# board2-4layer.net
KiCad netlist of a schematic drawn in EAGLE
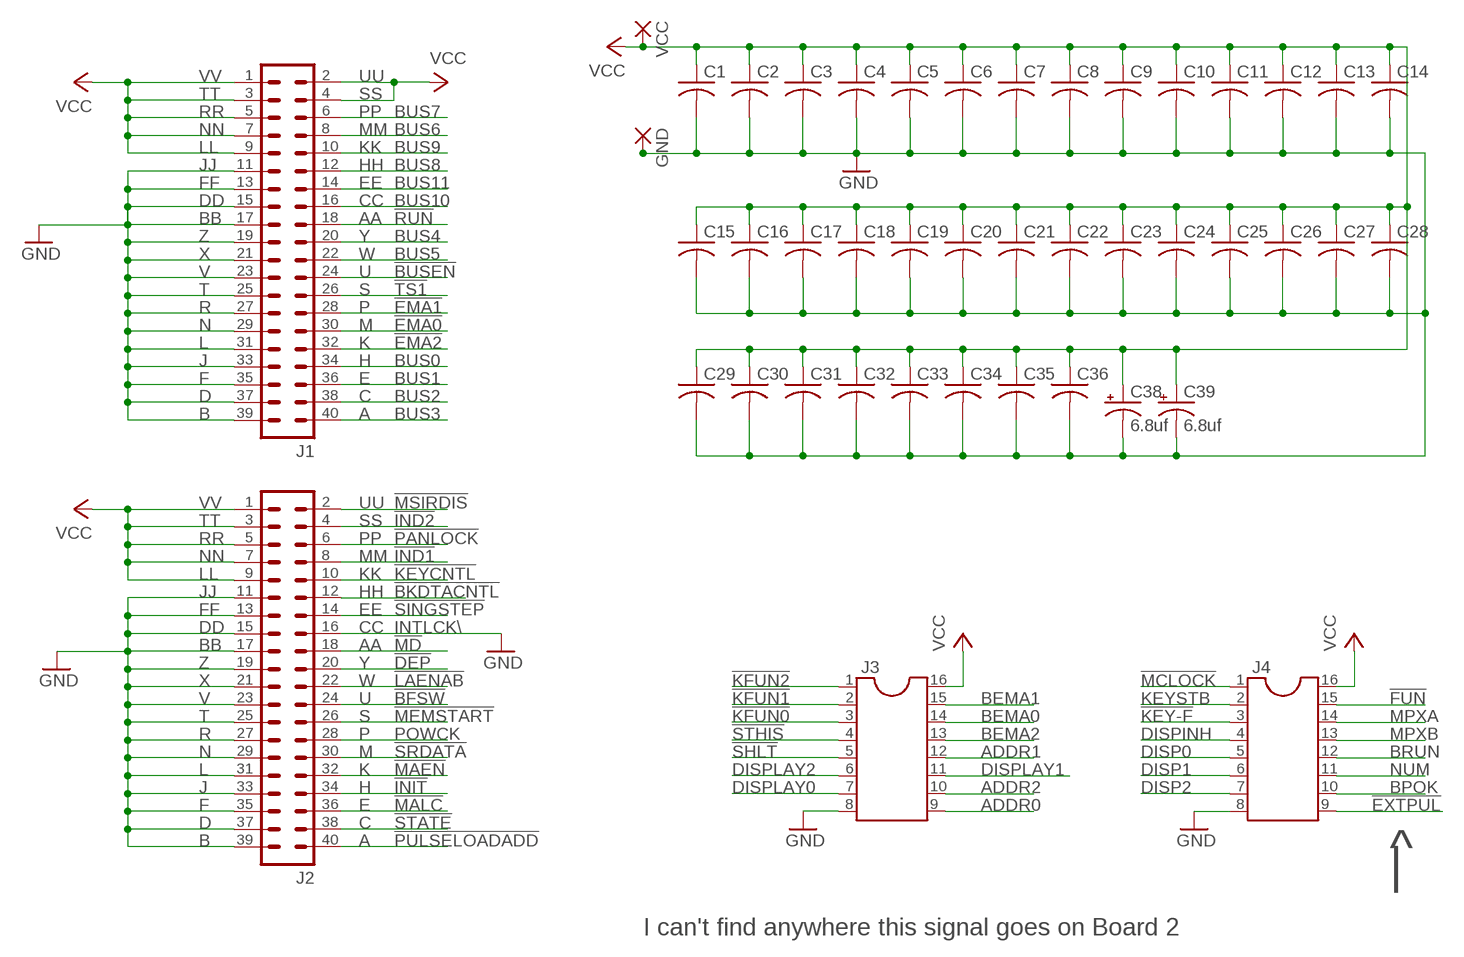
[diagram p0: schematic, sheet 1]
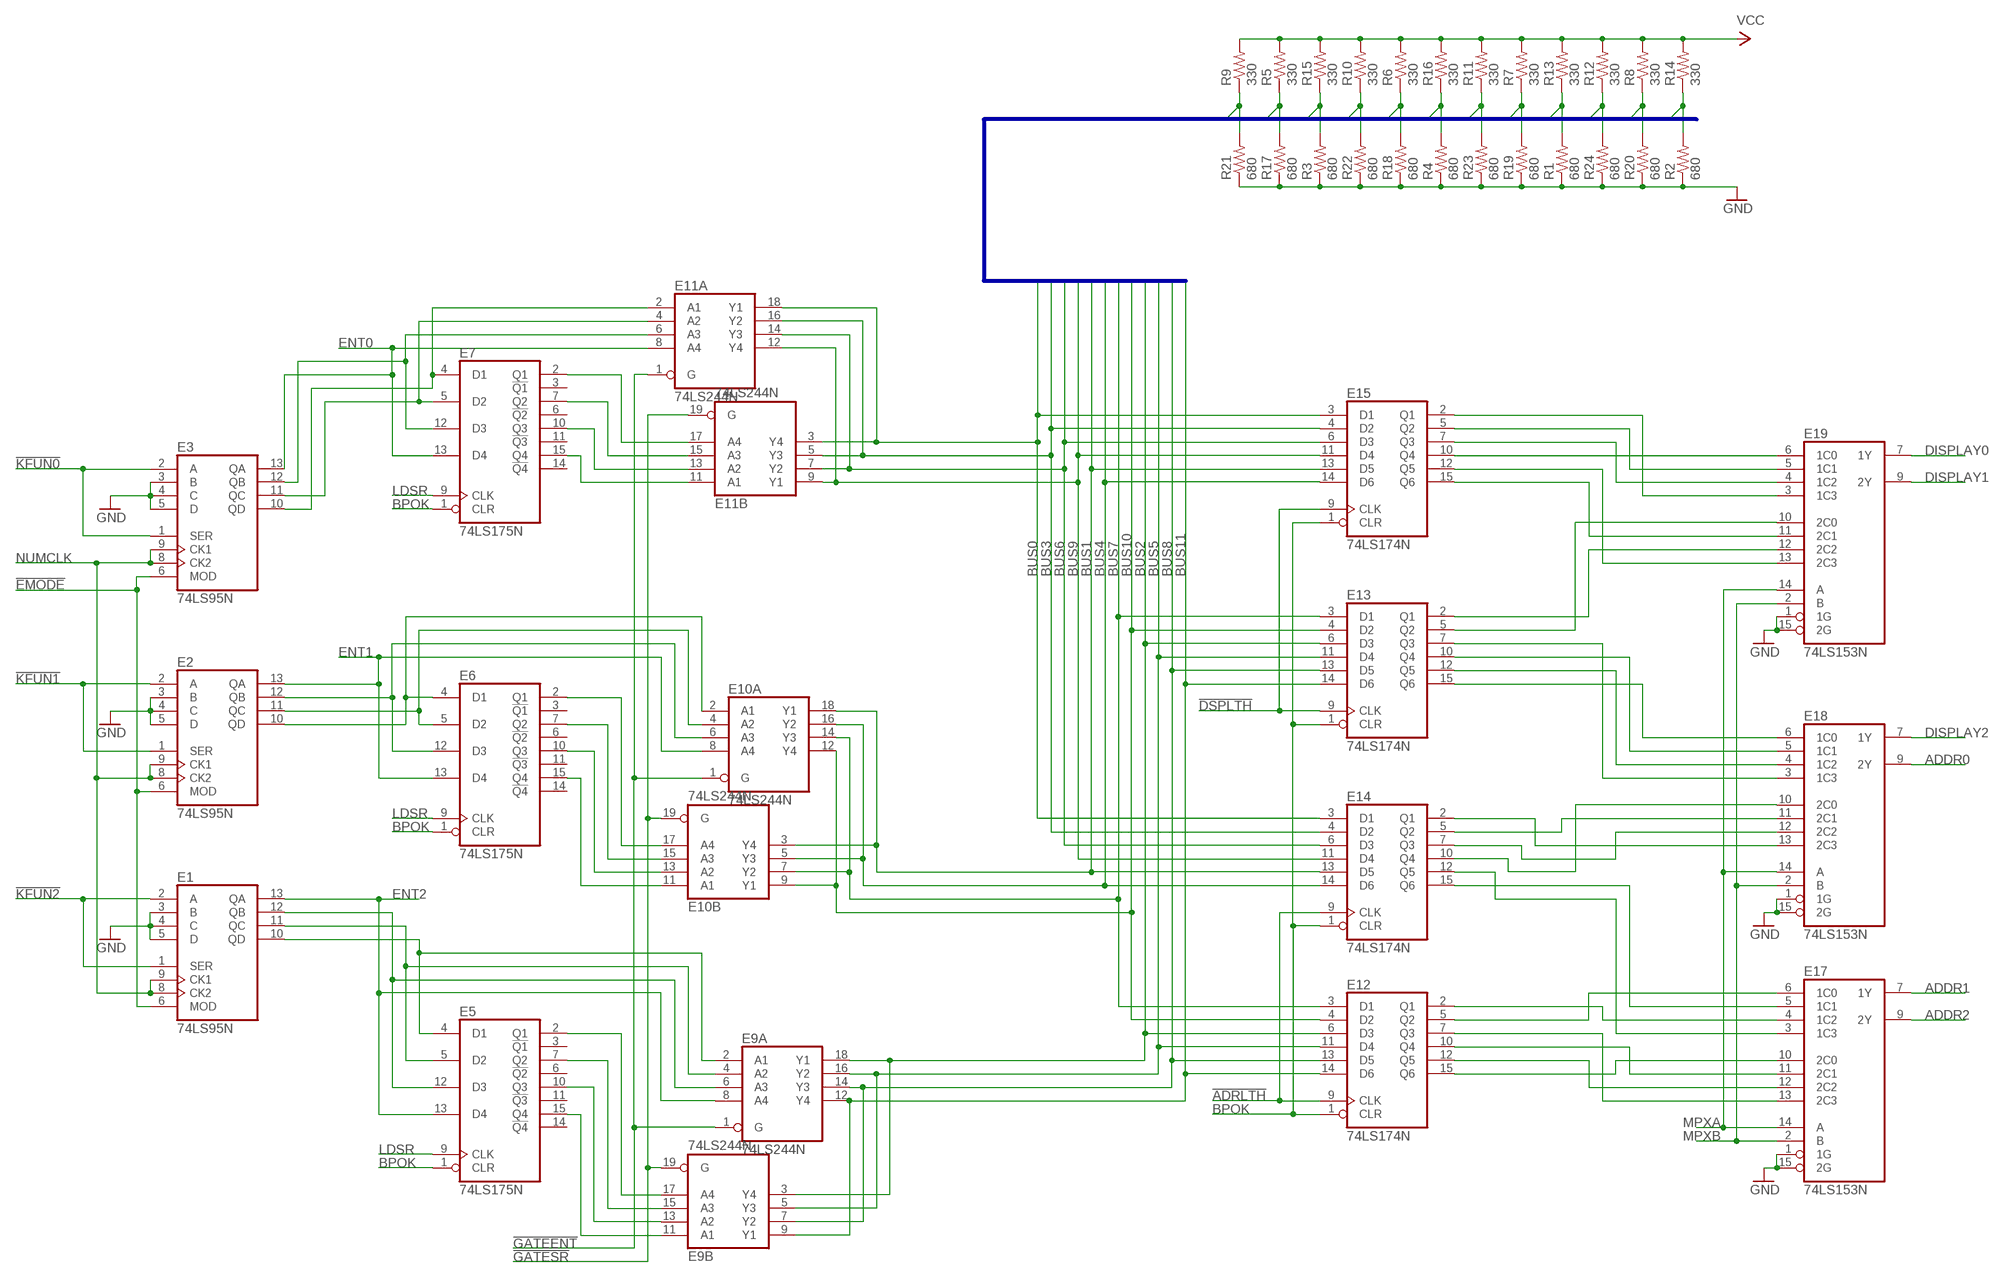
[diagram p1: schematic, sheet 2]
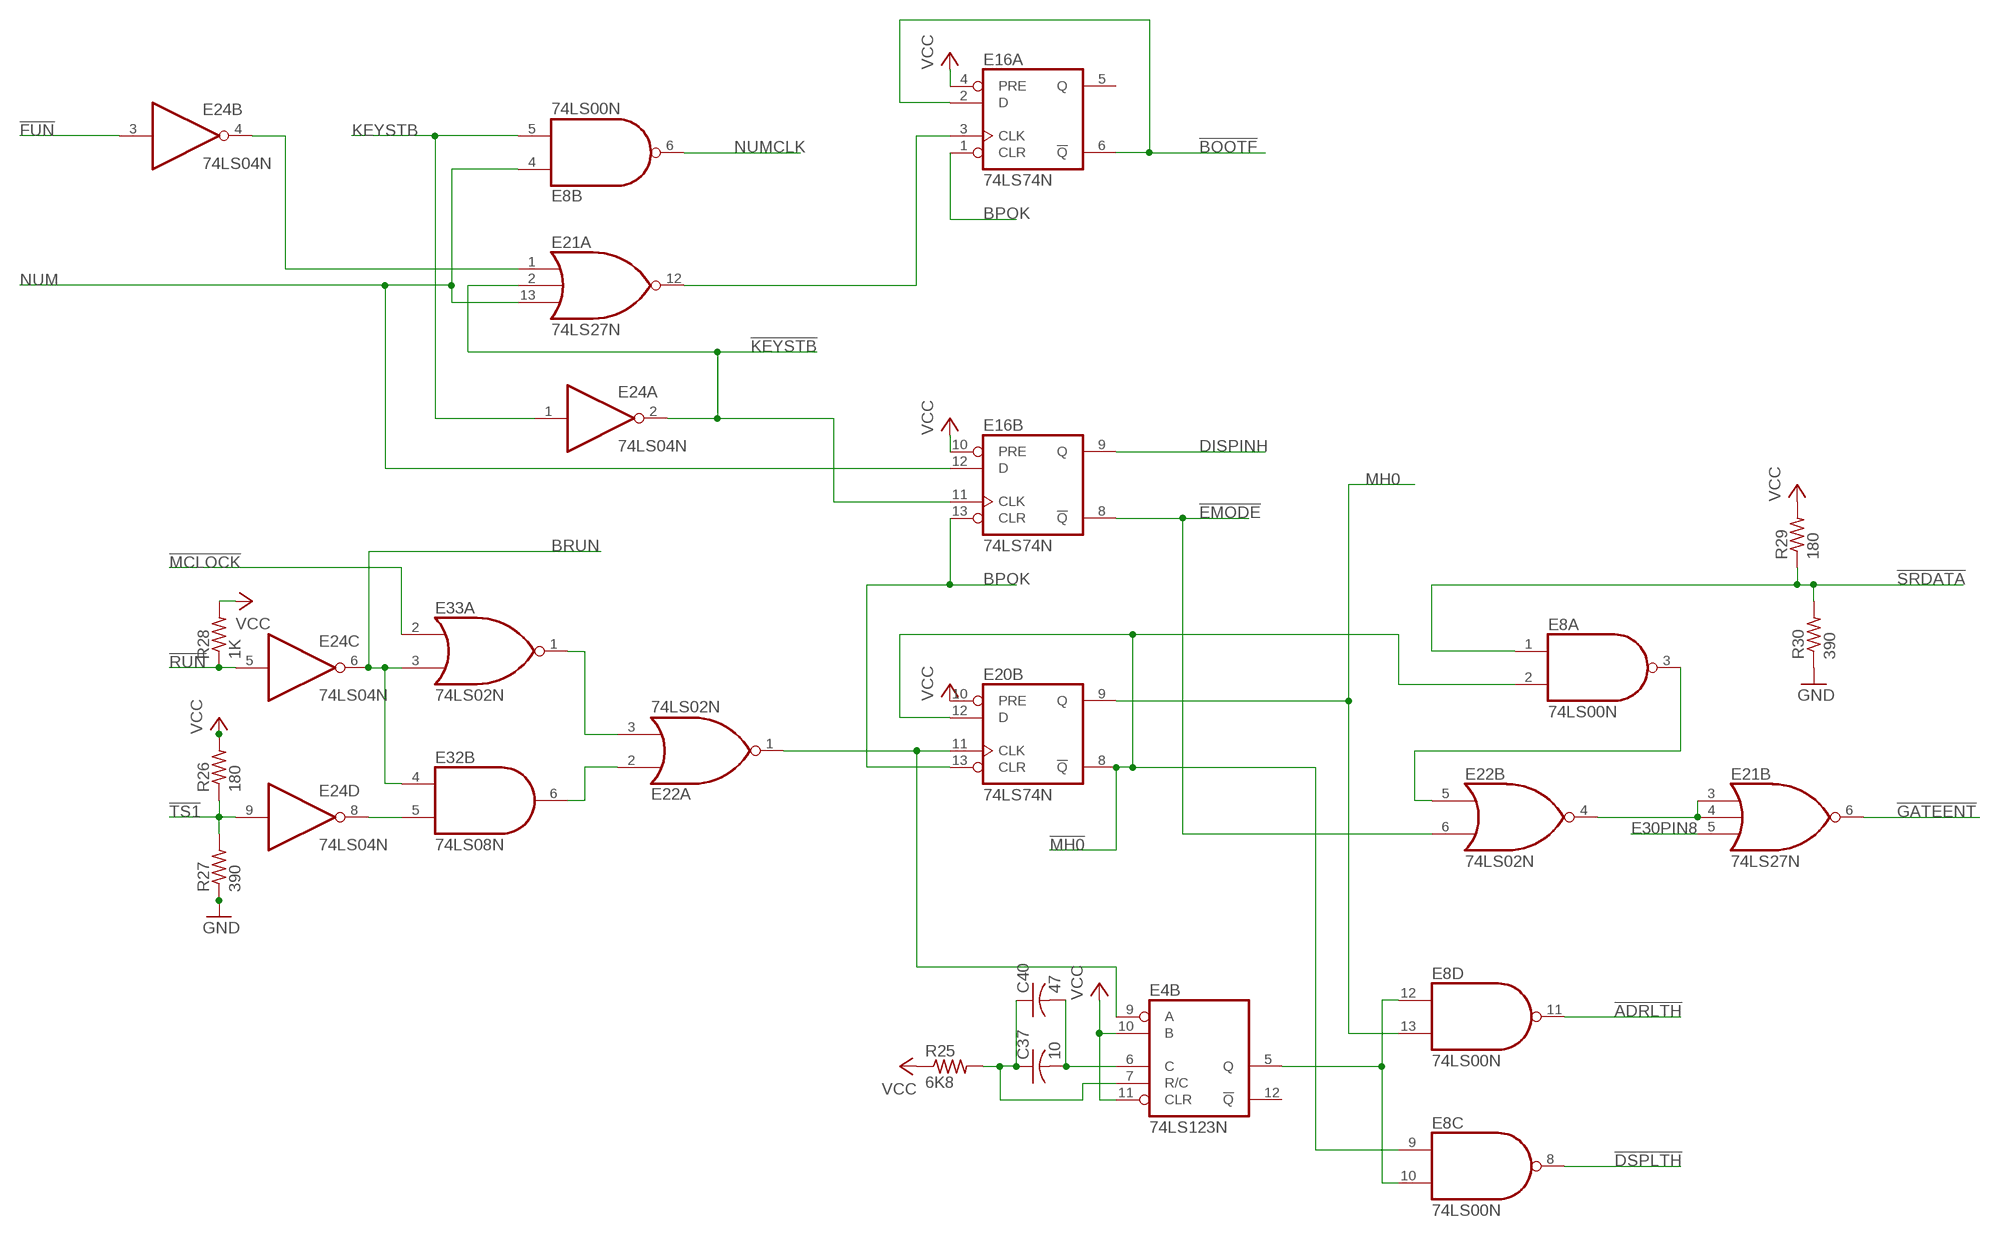
[diagram p2: schematic, sheet 3]
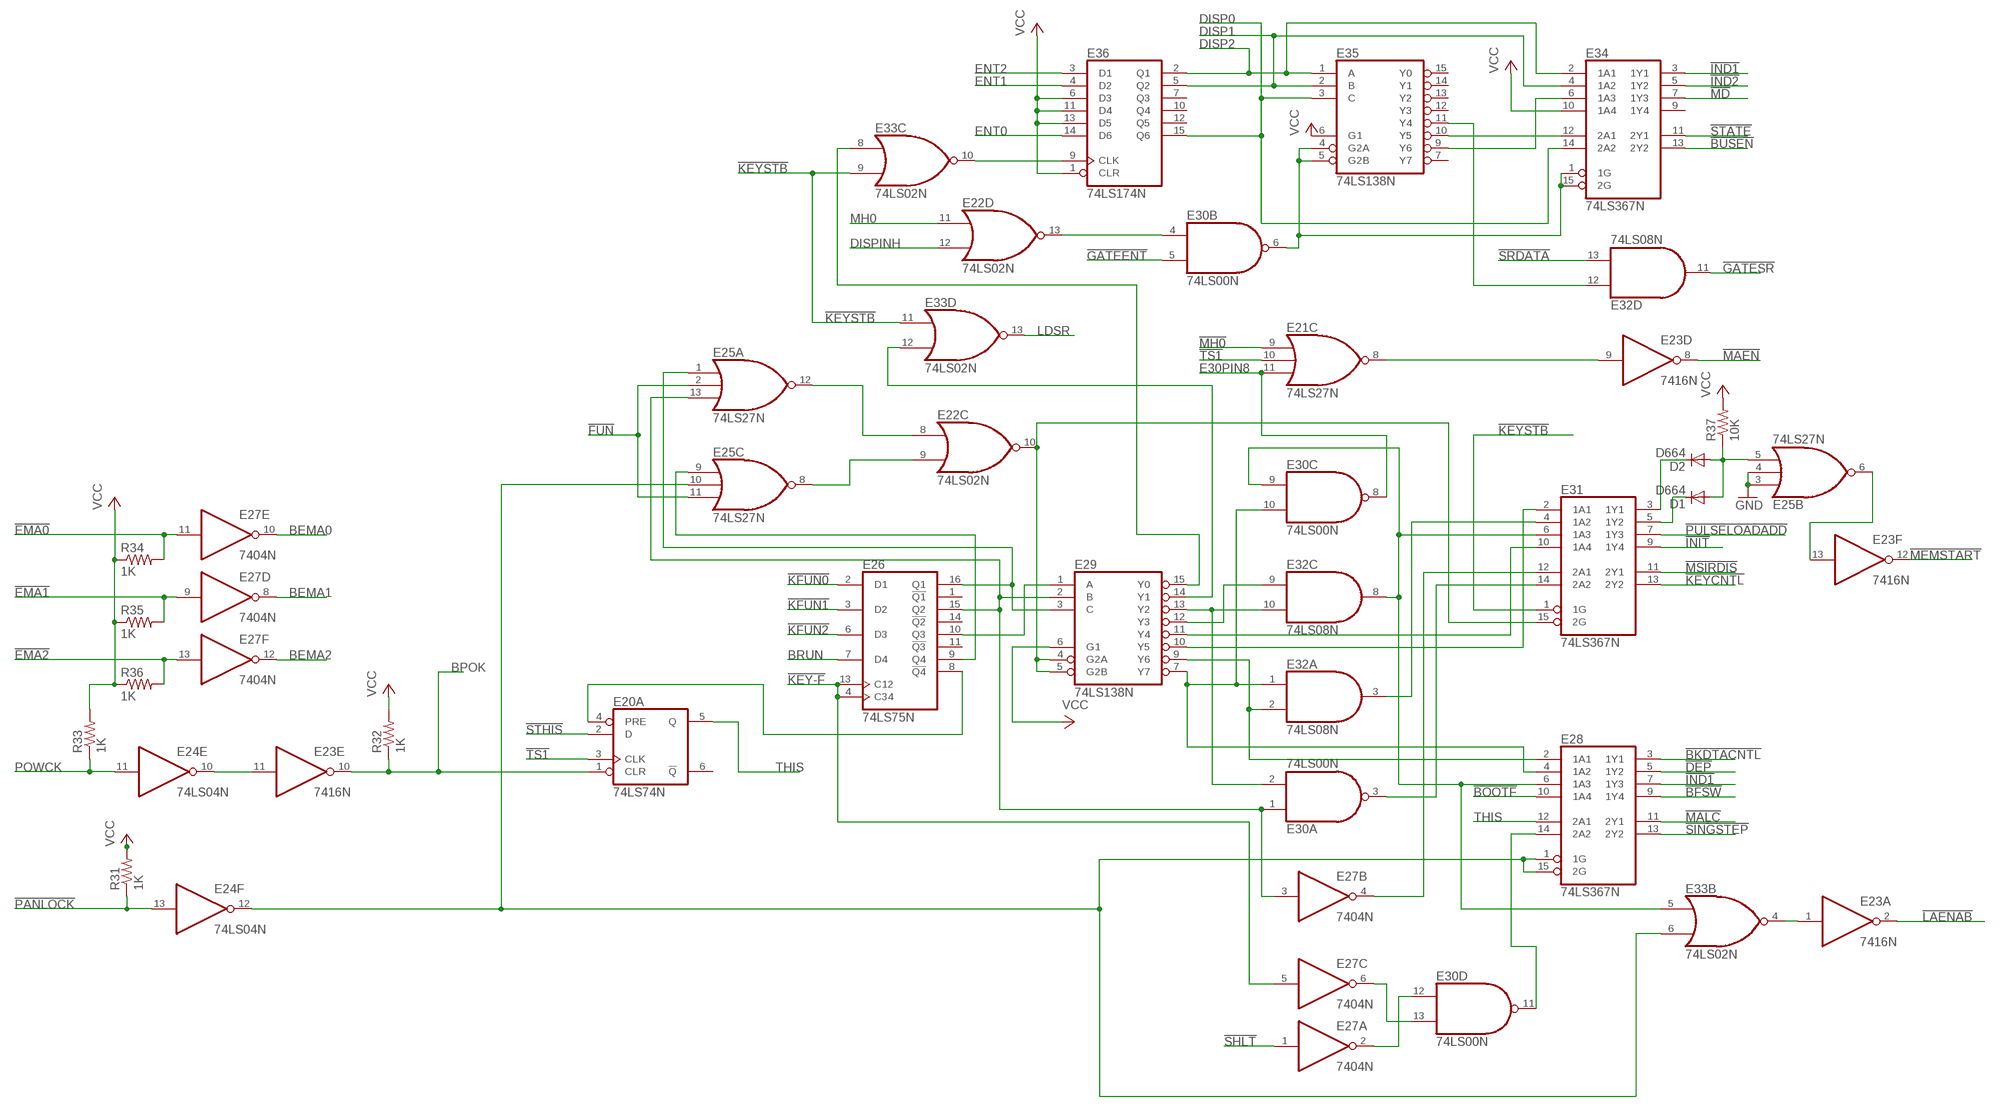
[diagram p3: schematic, sheet 4]

(export (version "E")
  (design (tool "Eeschema 10.0.6"))
  (components
    (comp (ref "C37")
      (value "10")
      (footprint "eagle-import:C050-025X075")
      (libsource (lib "eagle-import") (part "C-US050-025X075"))
    )
    (comp (ref "C40")
      (value "47")
      (footprint "eagle-import:C050-025X075")
      (libsource (lib "eagle-import") (part "C-US050-025X075"))
    )
    (comp (ref "E4")
      (value "74LS123N")
      (footprint "eagle-import:DIL16")
      (libsource (lib "eagle-import") (part "74123NLS"))
    )
    (comp (ref "E8")
      (value "74LS00N")
      (footprint "eagle-import:DIL14")
      (libsource (lib "eagle-import") (part "7400NLS"))
    )
    (comp (ref "E16")
      (value "74LS74N")
      (footprint "eagle-import:DIL14")
      (libsource (lib "eagle-import") (part "7474NLS"))
    )
    (comp (ref "E20")
      (value "74LS74N")
      (footprint "eagle-import:DIL14")
      (libsource (lib "eagle-import") (part "7474NLS"))
    )
    (comp (ref "E21")
      (value "74LS27N")
      (footprint "eagle-import:DIL14")
      (libsource (lib "eagle-import") (part "7427NLS"))
    )
    (comp (ref "E22")
      (value "74LS02N")
      (footprint "eagle-import:DIL14")
      (libsource (lib "eagle-import") (part "7402NLS"))
    )
    (comp (ref "E24")
      (value "74LS04N")
      (footprint "eagle-import:DIL14")
      (libsource (lib "eagle-import") (part "7404NLS"))
    )
    (comp (ref "E32")
      (value "74LS08N")
      (footprint "eagle-import:DIL14")
      (libsource (lib "eagle-import") (part "7408NLS"))
    )
    (comp (ref "E33")
      (value "74LS02N")
      (footprint "eagle-import:DIL14")
      (libsource (lib "eagle-import") (part "7402NLS"))
    )
    (comp (ref "R25")
      (value "6K8")
      (footprint "eagle-import:0207_10")
      (libsource (lib "eagle-import") (part "R-US_0207/10"))
    )
    (comp (ref "R26")
      (value "180")
      (footprint "eagle-import:0207_10")
      (libsource (lib "eagle-import") (part "R-US_0207/10"))
    )
    (comp (ref "R27")
      (value "390")
      (footprint "eagle-import:0207_10")
      (libsource (lib "eagle-import") (part "R-US_0207/10"))
    )
    (comp (ref "R28")
      (value "1K")
      (footprint "eagle-import:0207_10")
      (libsource (lib "eagle-import") (part "R-US_0207/10"))
    )
    (comp (ref "R29")
      (value "180")
      (footprint "eagle-import:0207_10")
      (libsource (lib "eagle-import") (part "R-US_0207/10"))
    )
    (comp (ref "R30")
      (value "390")
      (footprint "eagle-import:0207_10")
      (libsource (lib "eagle-import") (part "R-US_0207/10"))
    )
    (comp (ref "D1")
      (value "D664")
      (footprint "eagle-import:DO35-10")
      (libsource (lib "eagle-import") (part "1N4148DO35-10"))
    )
    (comp (ref "D2")
      (value "D664")
      (footprint "eagle-import:DO35-10")
      (libsource (lib "eagle-import") (part "1N4148DO35-10"))
    )
    (comp (ref "E23")
      (value "7416N")
      (footprint "eagle-import:DIL14")
      (libsource (lib "eagle-import") (part "7416N"))
    )
    (comp (ref "E25")
      (value "74LS27N")
      (footprint "eagle-import:DIL14")
      (libsource (lib "eagle-import") (part "7427NLS"))
    )
    (comp (ref "E26")
      (value "74LS75N")
      (footprint "eagle-import:DIL16")
      (libsource (lib "eagle-import") (part "7475NLS"))
    )
    (comp (ref "E27")
      (value "7404N")
      (footprint "eagle-import:DIL14")
      (libsource (lib "eagle-import") (part "7404N"))
    )
    (comp (ref "E28")
      (value "74LS367N")
      (footprint "eagle-import:DIL16")
      (libsource (lib "eagle-import") (part "74367N"))
    )
    (comp (ref "E29")
      (value "74LS138N")
      (footprint "eagle-import:DIL16")
      (libsource (lib "eagle-import") (part "74138NLS"))
    )
    (comp (ref "E30")
      (value "74LS00N")
      (footprint "eagle-import:DIL14")
      (libsource (lib "eagle-import") (part "7400NLS"))
    )
    (comp (ref "E31")
      (value "74LS367N")
      (footprint "eagle-import:DIL16")
      (libsource (lib "eagle-import") (part "74367N"))
    )
    (comp (ref "E34")
      (value "74LS367N")
      (footprint "eagle-import:DIL16")
      (libsource (lib "eagle-import") (part "74367N"))
    )
    (comp (ref "E35")
      (value "74LS138N")
      (footprint "eagle-import:DIL16")
      (libsource (lib "eagle-import") (part "74138NLS"))
    )
    (comp (ref "E36")
      (value "74LS174N")
      (footprint "eagle-import:DIL16")
      (libsource (lib "eagle-import") (part "74174NLS"))
    )
    (comp (ref "R31")
      (value "1K")
      (footprint "eagle-import:0207_10")
      (libsource (lib "eagle-import") (part "R-US_0207/10"))
    )
    (comp (ref "R32")
      (value "1K")
      (footprint "eagle-import:0207_10")
      (libsource (lib "eagle-import") (part "R-US_0207/10"))
    )
    (comp (ref "R33")
      (value "1K")
      (footprint "eagle-import:0207_10")
      (libsource (lib "eagle-import") (part "R-US_0207/10"))
    )
    (comp (ref "R34")
      (value "1K")
      (footprint "eagle-import:0207_10")
      (libsource (lib "eagle-import") (part "R-US_0207/10"))
    )
    (comp (ref "R35")
      (value "1K")
      (footprint "eagle-import:0207_10")
      (libsource (lib "eagle-import") (part "R-US_0207/10"))
    )
    (comp (ref "R36")
      (value "1K")
      (footprint "eagle-import:0207_10")
      (libsource (lib "eagle-import") (part "R-US_0207/10"))
    )
    (comp (ref "R37")
      (value "10K")
      (footprint "eagle-import:0207_10")
      (libsource (lib "eagle-import") (part "R-US_0207/10"))
    )
    (comp (ref "C1")
      (value "C-US050-025X075")
      (footprint "eagle-import:C050-025X075")
      (libsource (lib "eagle-import") (part "C-US050-025X075"))
    )
    (comp (ref "C2")
      (value "C-US050-025X075")
      (footprint "eagle-import:C050-025X075")
      (libsource (lib "eagle-import") (part "C-US050-025X075"))
    )
    (comp (ref "C3")
      (value "C-US050-025X075")
      (footprint "eagle-import:C050-025X075")
      (libsource (lib "eagle-import") (part "C-US050-025X075"))
    )
    (comp (ref "C4")
      (value "C-US050-025X075")
      (footprint "eagle-import:C050-025X075")
      (libsource (lib "eagle-import") (part "C-US050-025X075"))
    )
    (comp (ref "C5")
      (value "C-US050-025X075")
      (footprint "eagle-import:C050-025X075")
      (libsource (lib "eagle-import") (part "C-US050-025X075"))
    )
    (comp (ref "C6")
      (value "C-US050-025X075")
      (footprint "eagle-import:C050-025X075")
      (libsource (lib "eagle-import") (part "C-US050-025X075"))
    )
    (comp (ref "C7")
      (value "C-US050-025X075")
      (footprint "eagle-import:C050-025X075")
      (libsource (lib "eagle-import") (part "C-US050-025X075"))
    )
    (comp (ref "C8")
      (value "C-US050-025X075")
      (footprint "eagle-import:C050-025X075")
      (libsource (lib "eagle-import") (part "C-US050-025X075"))
    )
    (comp (ref "C9")
      (value "C-US050-025X075")
      (footprint "eagle-import:C050-025X075")
      (libsource (lib "eagle-import") (part "C-US050-025X075"))
    )
    (comp (ref "C10")
      (value "C-US050-025X075")
      (footprint "eagle-import:C050-025X075")
      (libsource (lib "eagle-import") (part "C-US050-025X075"))
    )
    (comp (ref "C11")
      (value "C-US050-025X075")
      (footprint "eagle-import:C050-025X075")
      (libsource (lib "eagle-import") (part "C-US050-025X075"))
    )
    (comp (ref "C12")
      (value "C-US050-025X075")
      (footprint "eagle-import:C050-025X075")
      (libsource (lib "eagle-import") (part "C-US050-025X075"))
    )
    (comp (ref "C13")
      (value "C-US050-025X075")
      (footprint "eagle-import:C050-025X075")
      (libsource (lib "eagle-import") (part "C-US050-025X075"))
    )
    (comp (ref "C14")
      (value "C-US050-025X075")
      (footprint "eagle-import:C050-025X075")
      (libsource (lib "eagle-import") (part "C-US050-025X075"))
    )
    (comp (ref "C15")
      (value "C-US050-025X075")
      (footprint "eagle-import:C050-025X075")
      (libsource (lib "eagle-import") (part "C-US050-025X075"))
    )
    (comp (ref "C16")
      (value "C-US050-025X075")
      (footprint "eagle-import:C050-025X075")
      (libsource (lib "eagle-import") (part "C-US050-025X075"))
    )
    (comp (ref "C17")
      (value "C-US050-025X075")
      (footprint "eagle-import:C050-025X075")
      (libsource (lib "eagle-import") (part "C-US050-025X075"))
    )
    (comp (ref "C18")
      (value "C-US050-025X075")
      (footprint "eagle-import:C050-025X075")
      (libsource (lib "eagle-import") (part "C-US050-025X075"))
    )
    (comp (ref "C19")
      (value "C-US050-025X075")
      (footprint "eagle-import:C050-025X075")
      (libsource (lib "eagle-import") (part "C-US050-025X075"))
    )
    (comp (ref "C20")
      (value "C-US050-025X075")
      (footprint "eagle-import:C050-025X075")
      (libsource (lib "eagle-import") (part "C-US050-025X075"))
    )
    (comp (ref "C21")
      (value "C-US050-025X075")
      (footprint "eagle-import:C050-025X075")
      (libsource (lib "eagle-import") (part "C-US050-025X075"))
    )
    (comp (ref "C22")
      (value "C-US050-025X075")
      (footprint "eagle-import:C050-025X075")
      (libsource (lib "eagle-import") (part "C-US050-025X075"))
    )
    (comp (ref "C23")
      (value "C-US050-025X075")
      (footprint "eagle-import:C050-025X075")
      (libsource (lib "eagle-import") (part "C-US050-025X075"))
    )
    (comp (ref "C24")
      (value "C-US050-025X075")
      (footprint "eagle-import:C050-025X075")
      (libsource (lib "eagle-import") (part "C-US050-025X075"))
    )
    (comp (ref "C25")
      (value "C-US050-025X075")
      (footprint "eagle-import:C050-025X075")
      (libsource (lib "eagle-import") (part "C-US050-025X075"))
    )
    (comp (ref "C26")
      (value "C-US050-025X075")
      (footprint "eagle-import:C050-025X075")
      (libsource (lib "eagle-import") (part "C-US050-025X075"))
    )
    (comp (ref "C27")
      (value "C-US050-025X075")
      (footprint "eagle-import:C050-025X075")
      (libsource (lib "eagle-import") (part "C-US050-025X075"))
    )
    (comp (ref "C28")
      (value "C-US050-025X075")
      (footprint "eagle-import:C050-025X075")
      (libsource (lib "eagle-import") (part "C-US050-025X075"))
    )
    (comp (ref "C29")
      (value "C-US050-025X075")
      (footprint "eagle-import:C050-025X075")
      (libsource (lib "eagle-import") (part "C-US050-025X075"))
    )
    (comp (ref "C30")
      (value "C-US050-025X075")
      (footprint "eagle-import:C050-025X075")
      (libsource (lib "eagle-import") (part "C-US050-025X075"))
    )
    (comp (ref "C31")
      (value "C-US050-025X075")
      (footprint "eagle-import:C050-025X075")
      (libsource (lib "eagle-import") (part "C-US050-025X075"))
    )
    (comp (ref "C32")
      (value "C-US050-025X075")
      (footprint "eagle-import:C050-025X075")
      (libsource (lib "eagle-import") (part "C-US050-025X075"))
    )
    (comp (ref "C33")
      (value "C-US050-025X075")
      (footprint "eagle-import:C050-025X075")
      (libsource (lib "eagle-import") (part "C-US050-025X075"))
    )
    (comp (ref "C34")
      (value "C-US050-025X075")
      (footprint "eagle-import:C050-025X075")
      (libsource (lib "eagle-import") (part "C-US050-025X075"))
    )
    (comp (ref "C35")
      (value "C-US050-025X075")
      (footprint "eagle-import:C050-025X075")
      (libsource (lib "eagle-import") (part "C-US050-025X075"))
    )
    (comp (ref "C36")
      (value "C-US050-025X075")
      (footprint "eagle-import:C050-025X075")
      (libsource (lib "eagle-import") (part "C-US050-025X075"))
    )
    (comp (ref "C38")
      (value "6.8uf")
      (footprint "eagle-import:E15-5")
      (libsource (lib "eagle-import") (part "CPOL-USE15-5AXIAL"))
    )
    (comp (ref "C39")
      (value "6.8uf")
      (footprint "eagle-import:E15-5")
      (libsource (lib "eagle-import") (part "CPOL-USE15-5AXIAL"))
    )
    (comp (ref "GND")
      (value "3,81/1,4")
      (footprint "eagle-import:3,81_1,4")
      (libsource (lib "eagle-import") (part "3,81/1,4"))
    )
    (comp (ref "J1")
      (value "40H")
      (footprint "eagle-import:40H")
      (libsource (lib "eagle-import") (part "40H"))
    )
    (comp (ref "J2")
      (value "40H")
      (footprint "eagle-import:40H")
      (libsource (lib "eagle-import") (part "40H"))
    )
    (comp (ref "J3")
      (value "DIL16S")
      (footprint "eagle-import:SOCKET-16")
      (libsource (lib "eagle-import") (part "DIL16S"))
    )
    (comp (ref "J4")
      (value "DIL16S")
      (footprint "eagle-import:SOCKET-16")
      (libsource (lib "eagle-import") (part "DIL16S"))
    )
    (comp (ref "VCC")
      (value "3,81/1,4")
      (footprint "eagle-import:3,81_1,4")
      (libsource (lib "eagle-import") (part "3,81/1,4"))
    )
    (comp (ref "E1")
      (value "74LS95N")
      (footprint "eagle-import:DIL14")
      (libsource (lib "eagle-import") (part "7495NLS"))
    )
    (comp (ref "E2")
      (value "74LS95N")
      (footprint "eagle-import:DIL14")
      (libsource (lib "eagle-import") (part "7495NLS"))
    )
    (comp (ref "E3")
      (value "74LS95N")
      (footprint "eagle-import:DIL14")
      (libsource (lib "eagle-import") (part "7495NLS"))
    )
    (comp (ref "E5")
      (value "74LS175N")
      (footprint "eagle-import:DIL16")
      (libsource (lib "eagle-import") (part "74175NLS"))
    )
    (comp (ref "E6")
      (value "74LS175N")
      (footprint "eagle-import:DIL16")
      (libsource (lib "eagle-import") (part "74175NLS"))
    )
    (comp (ref "E7")
      (value "74LS175N")
      (footprint "eagle-import:DIL16")
      (libsource (lib "eagle-import") (part "74175NLS"))
    )
    (comp (ref "E9")
      (value "74LS244N")
      (footprint "eagle-import:DIL20")
      (libsource (lib "eagle-import") (part "74244NS"))
    )
    (comp (ref "E10")
      (value "74LS244N")
      (footprint "eagle-import:DIL20")
      (libsource (lib "eagle-import") (part "74244NS"))
    )
    (comp (ref "E11")
      (value "74LS244N")
      (footprint "eagle-import:DIL20")
      (libsource (lib "eagle-import") (part "74244NS"))
    )
    (comp (ref "E12")
      (value "74LS174N")
      (footprint "eagle-import:DIL16")
      (libsource (lib "eagle-import") (part "74174NLS"))
    )
    (comp (ref "E13")
      (value "74LS174N")
      (footprint "eagle-import:DIL16")
      (libsource (lib "eagle-import") (part "74174NLS"))
    )
    (comp (ref "E14")
      (value "74LS174N")
      (footprint "eagle-import:DIL16")
      (libsource (lib "eagle-import") (part "74174NLS"))
    )
    (comp (ref "E15")
      (value "74LS174N")
      (footprint "eagle-import:DIL16")
      (libsource (lib "eagle-import") (part "74174NLS"))
    )
    (comp (ref "E17")
      (value "74LS153N")
      (footprint "eagle-import:DIL16")
      (libsource (lib "eagle-import") (part "74153NLS"))
    )
    (comp (ref "E18")
      (value "74LS153N")
      (footprint "eagle-import:DIL16")
      (libsource (lib "eagle-import") (part "74153NLS"))
    )
    (comp (ref "E19")
      (value "74LS153N")
      (footprint "eagle-import:DIL16")
      (libsource (lib "eagle-import") (part "74153NLS"))
    )
    (comp (ref "R1")
      (value "680")
      (footprint "eagle-import:0207_10")
      (libsource (lib "eagle-import") (part "R-US_0207/10"))
    )
    (comp (ref "R2")
      (value "680")
      (footprint "eagle-import:0207_10")
      (libsource (lib "eagle-import") (part "R-US_0207/10"))
    )
    (comp (ref "R3")
      (value "680")
      (footprint "eagle-import:0207_10")
      (libsource (lib "eagle-import") (part "R-US_0207/10"))
    )
    (comp (ref "R4")
      (value "680")
      (footprint "eagle-import:0207_10")
      (libsource (lib "eagle-import") (part "R-US_0207/10"))
    )
    (comp (ref "R5")
      (value "330")
      (footprint "eagle-import:0207_10")
      (libsource (lib "eagle-import") (part "R-US_0207/10"))
    )
    (comp (ref "R6")
      (value "330")
      (footprint "eagle-import:0207_10")
      (libsource (lib "eagle-import") (part "R-US_0207/10"))
    )
    (comp (ref "R7")
      (value "330")
      (footprint "eagle-import:0207_10")
      (libsource (lib "eagle-import") (part "R-US_0207/10"))
    )
    (comp (ref "R8")
      (value "330")
      (footprint "eagle-import:0207_10")
      (libsource (lib "eagle-import") (part "R-US_0207/10"))
    )
    (comp (ref "R9")
      (value "330")
      (footprint "eagle-import:0207_10")
      (libsource (lib "eagle-import") (part "R-US_0207/10"))
    )
    (comp (ref "R10")
      (value "330")
      (footprint "eagle-import:0207_10")
      (libsource (lib "eagle-import") (part "R-US_0207/10"))
    )
    (comp (ref "R11")
      (value "330")
      (footprint "eagle-import:0207_10")
      (libsource (lib "eagle-import") (part "R-US_0207/10"))
    )
    (comp (ref "R12")
      (value "330")
      (footprint "eagle-import:0207_10")
      (libsource (lib "eagle-import") (part "R-US_0207/10"))
    )
    (comp (ref "R13")
      (value "330")
      (footprint "eagle-import:0207_10")
      (libsource (lib "eagle-import") (part "R-US_0207/10"))
    )
    (comp (ref "R14")
      (value "330")
      (footprint "eagle-import:0207_10")
      (libsource (lib "eagle-import") (part "R-US_0207/10"))
    )
    (comp (ref "R15")
      (value "330")
      (footprint "eagle-import:0207_10")
      (libsource (lib "eagle-import") (part "R-US_0207/10"))
    )
    (comp (ref "R16")
      (value "330")
      (footprint "eagle-import:0207_10")
      (libsource (lib "eagle-import") (part "R-US_0207/10"))
    )
    (comp (ref "R17")
      (value "680")
      (footprint "eagle-import:0207_10")
      (libsource (lib "eagle-import") (part "R-US_0207/10"))
    )
    (comp (ref "R18")
      (value "680")
      (footprint "eagle-import:0207_10")
      (libsource (lib "eagle-import") (part "R-US_0207/10"))
    )
    (comp (ref "R19")
      (value "680")
      (footprint "eagle-import:0207_10")
      (libsource (lib "eagle-import") (part "R-US_0207/10"))
    )
    (comp (ref "R20")
      (value "680")
      (footprint "eagle-import:0207_10")
      (libsource (lib "eagle-import") (part "R-US_0207/10"))
    )
    (comp (ref "R21")
      (value "680")
      (footprint "eagle-import:0207_10")
      (libsource (lib "eagle-import") (part "R-US_0207/10"))
    )
    (comp (ref "R22")
      (value "680")
      (footprint "eagle-import:0207_10")
      (libsource (lib "eagle-import") (part "R-US_0207/10"))
    )
    (comp (ref "R23")
      (value "680")
      (footprint "eagle-import:0207_10")
      (libsource (lib "eagle-import") (part "R-US_0207/10"))
    )
    (comp (ref "R24")
      (value "680")
      (footprint "eagle-import:0207_10")
      (libsource (lib "eagle-import") (part "R-US_0207/10"))
    )
  )
  (nets
    (net (code "1") (name "ADDR0") (class "Default")
      (node (ref "E18") (pin "9") (pinfunction "2Y_9") (pintype "output"))
      (node (ref "J3") (pin "9") (pinfunction "9_9") (pintype "passive"))
    )
    (net (code "2") (name "ADDR1") (class "Default")
      (node (ref "E17") (pin "7") (pinfunction "1Y_7") (pintype "output"))
      (node (ref "J3") (pin "12") (pinfunction "12_12") (pintype "passive"))
    )
    (net (code "3") (name "ADDR2") (class "Default")
      (node (ref "E17") (pin "9") (pinfunction "2Y_9") (pintype "output"))
      (node (ref "J3") (pin "10") (pinfunction "10_10") (pintype "passive"))
    )
    (net (code "4") (name "BEMA0") (class "Default")
      (node (ref "E27") (pin "10") (pinfunction "O_10") (pintype "output"))
      (node (ref "J3") (pin "14") (pinfunction "14_14") (pintype "passive"))
    )
    (net (code "5") (name "BEMA1") (class "Default")
      (node (ref "E27") (pin "8") (pinfunction "O_8") (pintype "output"))
      (node (ref "J3") (pin "15") (pinfunction "15_15") (pintype "passive"))
    )
    (net (code "6") (name "BEMA2") (class "Default")
      (node (ref "E27") (pin "12") (pinfunction "O_12") (pintype "output"))
      (node (ref "J3") (pin "13") (pinfunction "13_13") (pintype "passive"))
    )
    (net (code "7") (name "BPOK") (class "Default")
      (node (ref "E12") (pin "1") (pinfunction "CLR_1") (pintype "input"))
      (node (ref "E13") (pin "1") (pinfunction "CLR_1") (pintype "input"))
      (node (ref "E14") (pin "1") (pinfunction "CLR_1") (pintype "input"))
      (node (ref "E15") (pin "1") (pinfunction "CLR_1") (pintype "input"))
      (node (ref "E16") (pin "1") (pinfunction "CLR_1") (pintype "input"))
      (node (ref "E16") (pin "13") (pinfunction "CLR_13") (pintype "input"))
      (node (ref "E20") (pin "1") (pinfunction "CLR_1") (pintype "input"))
      (node (ref "E20") (pin "13") (pinfunction "CLR_13") (pintype "input"))
      (node (ref "E23") (pin "10") (pinfunction "O_10") (pintype "open_collector"))
      (node (ref "E5") (pin "1") (pinfunction "CLR_1") (pintype "input"))
      (node (ref "E6") (pin "1") (pinfunction "CLR_1") (pintype "input"))
      (node (ref "E7") (pin "1") (pinfunction "CLR_1") (pintype "input"))
      (node (ref "J4") (pin "10") (pinfunction "10_10") (pintype "passive"))
      (node (ref "R32") (pin "1") (pinfunction "1_1") (pintype "passive"))
    )
    (net (code "8") (name "BRUN") (class "Default")
      (node (ref "E24") (pin "6") (pinfunction "O_6") (pintype "output"))
      (node (ref "E26") (pin "7") (pinfunction "D4_7") (pintype "input"))
      (node (ref "E32") (pin "4") (pinfunction "I0_4") (pintype "input"))
      (node (ref "E33") (pin "3") (pinfunction "I1_3") (pintype "input"))
      (node (ref "J4") (pin "12") (pinfunction "12_12") (pintype "passive"))
    )
    (net (code "9") (name "BUS0") (class "Default")
      (node (ref "E11") (pin "18") (pinfunction "Y1_18") (pintype "tri_state"))
      (node (ref "E11") (pin "3") (pinfunction "Y4_3") (pintype "tri_state"))
      (node (ref "E14") (pin "3") (pinfunction "D1_3") (pintype "input"))
      (node (ref "E15") (pin "3") (pinfunction "D1_3") (pintype "input"))
      (node (ref "J1") (pin "34") (pinfunction "34_34") (pintype "passive"))
      (node (ref "R21") (pin "2") (pinfunction "2_2") (pintype "passive"))
      (node (ref "R9") (pin "1") (pinfunction "1_1") (pintype "passive"))
    )
    (net (code "10") (name "BUS1") (class "Default")
      (node (ref "E10") (pin "18") (pinfunction "Y1_18") (pintype "tri_state"))
      (node (ref "E10") (pin "3") (pinfunction "Y4_3") (pintype "tri_state"))
      (node (ref "E14") (pin "13") (pinfunction "D5_13") (pintype "input"))
      (node (ref "E15") (pin "13") (pinfunction "D5_13") (pintype "input"))
      (node (ref "J1") (pin "36") (pinfunction "36_36") (pintype "passive"))
      (node (ref "R17") (pin "2") (pinfunction "2_2") (pintype "passive"))
      (node (ref "R5") (pin "1") (pinfunction "1_1") (pintype "passive"))
    )
    (net (code "11") (name "BUS2") (class "Default")
      (node (ref "E12") (pin "6") (pinfunction "D3_6") (pintype "input"))
      (node (ref "E13") (pin "6") (pinfunction "D3_6") (pintype "input"))
      (node (ref "E9") (pin "18") (pinfunction "Y1_18") (pintype "tri_state"))
      (node (ref "E9") (pin "3") (pinfunction "Y4_3") (pintype "tri_state"))
      (node (ref "J1") (pin "38") (pinfunction "38_38") (pintype "passive"))
      (node (ref "R15") (pin "1") (pinfunction "1_1") (pintype "passive"))
      (node (ref "R3") (pin "2") (pinfunction "2_2") (pintype "passive"))
    )
    (net (code "12") (name "BUS3") (class "Default")
      (node (ref "E11") (pin "16") (pinfunction "Y2_16") (pintype "tri_state"))
      (node (ref "E11") (pin "5") (pinfunction "Y3_5") (pintype "tri_state"))
      (node (ref "E14") (pin "4") (pinfunction "D2_4") (pintype "input"))
      (node (ref "E15") (pin "4") (pinfunction "D2_4") (pintype "input"))
      (node (ref "J1") (pin "40") (pinfunction "40_40") (pintype "passive"))
      (node (ref "R10") (pin "1") (pinfunction "1_1") (pintype "passive"))
      (node (ref "R22") (pin "2") (pinfunction "2_2") (pintype "passive"))
    )
    (net (code "13") (name "BUS4") (class "Default")
      (node (ref "E10") (pin "16") (pinfunction "Y2_16") (pintype "tri_state"))
      (node (ref "E10") (pin "5") (pinfunction "Y3_5") (pintype "tri_state"))
      (node (ref "E14") (pin "14") (pinfunction "D6_14") (pintype "input"))
      (node (ref "E15") (pin "14") (pinfunction "D6_14") (pintype "input"))
      (node (ref "J1") (pin "20") (pinfunction "20_20") (pintype "passive"))
      (node (ref "R18") (pin "2") (pinfunction "2_2") (pintype "passive"))
      (node (ref "R6") (pin "1") (pinfunction "1_1") (pintype "passive"))
    )
    (net (code "14") (name "BUS5") (class "Default")
      (node (ref "E12") (pin "11") (pinfunction "D4_11") (pintype "input"))
      (node (ref "E13") (pin "11") (pinfunction "D4_11") (pintype "input"))
      (node (ref "E9") (pin "16") (pinfunction "Y2_16") (pintype "tri_state"))
      (node (ref "E9") (pin "5") (pinfunction "Y3_5") (pintype "tri_state"))
      (node (ref "J1") (pin "22") (pinfunction "22_22") (pintype "passive"))
      (node (ref "R16") (pin "1") (pinfunction "1_1") (pintype "passive"))
      (node (ref "R4") (pin "2") (pinfunction "2_2") (pintype "passive"))
    )
    (net (code "15") (name "BUS6") (class "Default")
      (node (ref "E11") (pin "14") (pinfunction "Y3_14") (pintype "tri_state"))
      (node (ref "E11") (pin "7") (pinfunction "Y2_7") (pintype "tri_state"))
      (node (ref "E14") (pin "6") (pinfunction "D3_6") (pintype "input"))
      (node (ref "E15") (pin "6") (pinfunction "D3_6") (pintype "input"))
      (node (ref "J1") (pin "8") (pinfunction "8_8") (pintype "passive"))
      (node (ref "R11") (pin "1") (pinfunction "1_1") (pintype "passive"))
      (node (ref "R23") (pin "2") (pinfunction "2_2") (pintype "passive"))
    )
    (net (code "16") (name "BUS7") (class "Default")
      (node (ref "E10") (pin "14") (pinfunction "Y3_14") (pintype "tri_state"))
      (node (ref "E10") (pin "7") (pinfunction "Y2_7") (pintype "tri_state"))
      (node (ref "E12") (pin "3") (pinfunction "D1_3") (pintype "input"))
      (node (ref "E13") (pin "3") (pinfunction "D1_3") (pintype "input"))
      (node (ref "J1") (pin "6") (pinfunction "6_6") (pintype "passive"))
      (node (ref "R19") (pin "2") (pinfunction "2_2") (pintype "passive"))
      (node (ref "R7") (pin "1") (pinfunction "1_1") (pintype "passive"))
    )
    (net (code "17") (name "BUS8") (class "Default")
      (node (ref "E12") (pin "13") (pinfunction "D5_13") (pintype "input"))
      (node (ref "E13") (pin "13") (pinfunction "D5_13") (pintype "input"))
      (node (ref "E9") (pin "14") (pinfunction "Y3_14") (pintype "tri_state"))
      (node (ref "E9") (pin "7") (pinfunction "Y2_7") (pintype "tri_state"))
      (node (ref "J1") (pin "12") (pinfunction "12_12") (pintype "passive"))
      (node (ref "R1") (pin "2") (pinfunction "2_2") (pintype "passive"))
      (node (ref "R13") (pin "1") (pinfunction "1_1") (pintype "passive"))
    )
    (net (code "18") (name "BUS9") (class "Default")
      (node (ref "E11") (pin "12") (pinfunction "Y4_12") (pintype "tri_state"))
      (node (ref "E11") (pin "9") (pinfunction "Y1_9") (pintype "tri_state"))
      (node (ref "E14") (pin "11") (pinfunction "D4_11") (pintype "input"))
      (node (ref "E15") (pin "11") (pinfunction "D4_11") (pintype "input"))
      (node (ref "J1") (pin "10") (pinfunction "10_10") (pintype "passive"))
      (node (ref "R12") (pin "1") (pinfunction "1_1") (pintype "passive"))
      (node (ref "R24") (pin "2") (pinfunction "2_2") (pintype "passive"))
    )
    (net (code "19") (name "BUS10") (class "Default")
      (node (ref "E10") (pin "12") (pinfunction "Y4_12") (pintype "tri_state"))
      (node (ref "E10") (pin "9") (pinfunction "Y1_9") (pintype "tri_state"))
      (node (ref "E12") (pin "4") (pinfunction "D2_4") (pintype "input"))
      (node (ref "E13") (pin "4") (pinfunction "D2_4") (pintype "input"))
      (node (ref "J1") (pin "16") (pinfunction "16_16") (pintype "passive"))
      (node (ref "R20") (pin "2") (pinfunction "2_2") (pintype "passive"))
      (node (ref "R8") (pin "1") (pinfunction "1_1") (pintype "passive"))
    )
    (net (code "20") (name "BUS11") (class "Default")
      (node (ref "E12") (pin "14") (pinfunction "D6_14") (pintype "input"))
      (node (ref "E13") (pin "14") (pinfunction "D6_14") (pintype "input"))
      (node (ref "E9") (pin "12") (pinfunction "Y4_12") (pintype "tri_state"))
      (node (ref "E9") (pin "9") (pinfunction "Y1_9") (pintype "tri_state"))
      (node (ref "J1") (pin "14") (pinfunction "14_14") (pintype "passive"))
      (node (ref "R14") (pin "1") (pinfunction "1_1") (pintype "passive"))
      (node (ref "R2") (pin "2") (pinfunction "2_2") (pintype "passive"))
    )
    (net (code "21") (name "DISP0") (class "Default")
      (node (ref "E34") (pin "14") (pinfunction "2A2_14") (pintype "input"))
      (node (ref "E35") (pin "3") (pinfunction "C_3") (pintype "input"))
      (node (ref "E36") (pin "15") (pinfunction "Q6_15") (pintype "output"))
      (node (ref "J4") (pin "5") (pinfunction "5_5") (pintype "passive"))
    )
    (net (code "22") (name "DISP1") (class "Default")
      (node (ref "E34") (pin "4") (pinfunction "1A2_4") (pintype "input"))
      (node (ref "E35") (pin "2") (pinfunction "B_2") (pintype "input"))
      (node (ref "E36") (pin "5") (pinfunction "Q2_5") (pintype "output"))
      (node (ref "J4") (pin "6") (pinfunction "6_6") (pintype "passive"))
    )
    (net (code "23") (name "DISP2") (class "Default")
      (node (ref "E34") (pin "2") (pinfunction "1A1_2") (pintype "input"))
      (node (ref "E35") (pin "1") (pinfunction "A_1") (pintype "input"))
      (node (ref "E36") (pin "2") (pinfunction "Q1_2") (pintype "output"))
      (node (ref "J4") (pin "7") (pinfunction "7_7") (pintype "passive"))
    )
    (net (code "24") (name "DISPINH") (class "Default")
      (node (ref "E16") (pin "9") (pinfunction "Q_9") (pintype "output"))
      (node (ref "E22") (pin "12") (pinfunction "I1_12") (pintype "input"))
      (node (ref "J4") (pin "4") (pinfunction "4_4") (pintype "passive"))
    )
    (net (code "25") (name "DISPLAY0") (class "Default")
      (node (ref "E19") (pin "7") (pinfunction "1Y_7") (pintype "output"))
      (node (ref "J3") (pin "7") (pinfunction "7_7") (pintype "passive"))
    )
    (net (code "26") (name "DISPLAY1") (class "Default")
      (node (ref "E19") (pin "9") (pinfunction "2Y_9") (pintype "output"))
      (node (ref "J3") (pin "11") (pinfunction "11_11") (pintype "passive"))
    )
    (net (code "27") (name "DISPLAY2") (class "Default")
      (node (ref "E18") (pin "7") (pinfunction "1Y_7") (pintype "output"))
      (node (ref "J3") (pin "6") (pinfunction "6_6") (pintype "passive"))
    )
    (net (code "28") (name "E30PIN8") (class "Default")
      (node (ref "E21") (pin "11") (pinfunction "I2_11") (pintype "input"))
      (node (ref "E21") (pin "5") (pinfunction "I2_5") (pintype "input"))
      (node (ref "E30") (pin "8") (pinfunction "O_8") (pintype "output"))
    )
    (net (code "29") (name "ENT0") (class "Default")
      (node (ref "E11") (pin "8") (pinfunction "A4_8") (pintype "input"))
      (node (ref "E3") (pin "13") (pinfunction "QA_13") (pintype "output"))
      (node (ref "E36") (pin "14") (pinfunction "D6_14") (pintype "input"))
      (node (ref "E7") (pin "13") (pinfunction "D4_13") (pintype "input"))
    )
    (net (code "30") (name "ENT1") (class "Default")
      (node (ref "E10") (pin "8") (pinfunction "A4_8") (pintype "input"))
      (node (ref "E2") (pin "13") (pinfunction "QA_13") (pintype "output"))
      (node (ref "E36") (pin "4") (pinfunction "D2_4") (pintype "input"))
      (node (ref "E6") (pin "13") (pinfunction "D4_13") (pintype "input"))
    )
    (net (code "31") (name "ENT2") (class "Default")
      (node (ref "E1") (pin "13") (pinfunction "QA_13") (pintype "output"))
      (node (ref "E36") (pin "3") (pinfunction "D1_3") (pintype "input"))
      (node (ref "E5") (pin "13") (pinfunction "D4_13") (pintype "input"))
      (node (ref "E9") (pin "8") (pinfunction "A4_8") (pintype "input"))
    )
    (net (code "32") (name "GND") (class "Default")
      (node (ref "C1") (pin "2") (pinfunction "2_2") (pintype "passive"))
      (node (ref "C10") (pin "2") (pinfunction "2_2") (pintype "passive"))
      (node (ref "C11") (pin "2") (pinfunction "2_2") (pintype "passive"))
      (node (ref "C12") (pin "2") (pinfunction "2_2") (pintype "passive"))
      (node (ref "C13") (pin "2") (pinfunction "2_2") (pintype "passive"))
      (node (ref "C14") (pin "2") (pinfunction "2_2") (pintype "passive"))
      (node (ref "C15") (pin "2") (pinfunction "2_2") (pintype "passive"))
      (node (ref "C16") (pin "2") (pinfunction "2_2") (pintype "passive"))
      (node (ref "C17") (pin "2") (pinfunction "2_2") (pintype "passive"))
      (node (ref "C18") (pin "2") (pinfunction "2_2") (pintype "passive"))
      (node (ref "C19") (pin "2") (pinfunction "2_2") (pintype "passive"))
      (node (ref "C2") (pin "2") (pinfunction "2_2") (pintype "passive"))
      (node (ref "C20") (pin "2") (pinfunction "2_2") (pintype "passive"))
      (node (ref "C21") (pin "2") (pinfunction "2_2") (pintype "passive"))
      (node (ref "C22") (pin "2") (pinfunction "2_2") (pintype "passive"))
      (node (ref "C23") (pin "2") (pinfunction "2_2") (pintype "passive"))
      (node (ref "C24") (pin "2") (pinfunction "2_2") (pintype "passive"))
      (node (ref "C25") (pin "2") (pinfunction "2_2") (pintype "passive"))
      (node (ref "C26") (pin "2") (pinfunction "2_2") (pintype "passive"))
      (node (ref "C27") (pin "2") (pinfunction "2_2") (pintype "passive"))
      (node (ref "C28") (pin "2") (pinfunction "2_2") (pintype "passive"))
      (node (ref "C29") (pin "2") (pinfunction "2_2") (pintype "passive"))
      (node (ref "C3") (pin "2") (pinfunction "2_2") (pintype "passive"))
      (node (ref "C30") (pin "2") (pinfunction "2_2") (pintype "passive"))
      (node (ref "C31") (pin "2") (pinfunction "2_2") (pintype "passive"))
      (node (ref "C32") (pin "2") (pinfunction "2_2") (pintype "passive"))
      (node (ref "C33") (pin "2") (pinfunction "2_2") (pintype "passive"))
      (node (ref "C34") (pin "2") (pinfunction "2_2") (pintype "passive"))
      (node (ref "C35") (pin "2") (pinfunction "2_2") (pintype "passive"))
      (node (ref "C36") (pin "2") (pinfunction "2_2") (pintype "passive"))
      (node (ref "C38") (pin "-") (pinfunction "-_-") (pintype "passive"))
      (node (ref "C39") (pin "-") (pinfunction "-_-") (pintype "passive"))
      (node (ref "C4") (pin "2") (pinfunction "2_2") (pintype "passive"))
      (node (ref "C5") (pin "2") (pinfunction "2_2") (pintype "passive"))
      (node (ref "C6") (pin "2") (pinfunction "2_2") (pintype "passive"))
      (node (ref "C7") (pin "2") (pinfunction "2_2") (pintype "passive"))
      (node (ref "C8") (pin "2") (pinfunction "2_2") (pintype "passive"))
      (node (ref "C9") (pin "2") (pinfunction "2_2") (pintype "passive"))
      (node (ref "E1") (pin "3") (pinfunction "B_3") (pintype "input"))
      (node (ref "E1") (pin "4") (pinfunction "C_4") (pintype "input"))
      (node (ref "E1") (pin "5") (pinfunction "D_5") (pintype "input"))
      (node (ref "E17") (pin "1") (pinfunction "1G_1") (pintype "input"))
      (node (ref "E17") (pin "15") (pinfunction "2G_15") (pintype "input"))
      (node (ref "E18") (pin "1") (pinfunction "1G_1") (pintype "input"))
      (node (ref "E18") (pin "15") (pinfunction "2G_15") (pintype "input"))
      (node (ref "E19") (pin "1") (pinfunction "1G_1") (pintype "input"))
      (node (ref "E19") (pin "15") (pinfunction "2G_15") (pintype "input"))
      (node (ref "E2") (pin "3") (pinfunction "B_3") (pintype "input"))
      (node (ref "E2") (pin "4") (pinfunction "C_4") (pintype "input"))
      (node (ref "E2") (pin "5") (pinfunction "D_5") (pintype "input"))
      (node (ref "E25") (pin "3") (pinfunction "I0_3") (pintype "input"))
      (node (ref "E25") (pin "4") (pinfunction "I1_4") (pintype "input"))
      (node (ref "E3") (pin "3") (pinfunction "B_3") (pintype "input"))
      (node (ref "E3") (pin "4") (pinfunction "C_4") (pintype "input"))
      (node (ref "E3") (pin "5") (pinfunction "D_5") (pintype "input"))
      (node (ref "GND") (pin "1") (pinfunction "P_1") (pintype "passive"))
      (node (ref "J1") (pin "11") (pinfunction "11_11") (pintype "passive"))
      (node (ref "J1") (pin "13") (pinfunction "13_13") (pintype "passive"))
      (node (ref "J1") (pin "15") (pinfunction "15_15") (pintype "passive"))
      (node (ref "J1") (pin "17") (pinfunction "17_17") (pintype "passive"))
      (node (ref "J1") (pin "19") (pinfunction "19_19") (pintype "passive"))
      (node (ref "J1") (pin "21") (pinfunction "21_21") (pintype "passive"))
      (node (ref "J1") (pin "23") (pinfunction "23_23") (pintype "passive"))
      (node (ref "J1") (pin "25") (pinfunction "25_25") (pintype "passive"))
      (node (ref "J1") (pin "27") (pinfunction "27_27") (pintype "passive"))
      (node (ref "J1") (pin "29") (pinfunction "29_29") (pintype "passive"))
      (node (ref "J1") (pin "31") (pinfunction "31_31") (pintype "passive"))
      (node (ref "J1") (pin "33") (pinfunction "33_33") (pintype "passive"))
      (node (ref "J1") (pin "35") (pinfunction "35_35") (pintype "passive"))
      (node (ref "J1") (pin "37") (pinfunction "37_37") (pintype "passive"))
      (node (ref "J1") (pin "39") (pinfunction "39_39") (pintype "passive"))
      (node (ref "J2") (pin "11") (pinfunction "11_11") (pintype "passive"))
      (node (ref "J2") (pin "13") (pinfunction "13_13") (pintype "passive"))
      (node (ref "J2") (pin "15") (pinfunction "15_15") (pintype "passive"))
      (node (ref "J2") (pin "16") (pinfunction "16_16") (pintype "passive"))
      (node (ref "J2") (pin "17") (pinfunction "17_17") (pintype "passive"))
      (node (ref "J2") (pin "19") (pinfunction "19_19") (pintype "passive"))
      (node (ref "J2") (pin "21") (pinfunction "21_21") (pintype "passive"))
      (node (ref "J2") (pin "23") (pinfunction "23_23") (pintype "passive"))
      (node (ref "J2") (pin "25") (pinfunction "25_25") (pintype "passive"))
      (node (ref "J2") (pin "27") (pinfunction "27_27") (pintype "passive"))
      (node (ref "J2") (pin "29") (pinfunction "29_29") (pintype "passive"))
      (node (ref "J2") (pin "31") (pinfunction "31_31") (pintype "passive"))
      (node (ref "J2") (pin "33") (pinfunction "33_33") (pintype "passive"))
      (node (ref "J2") (pin "35") (pinfunction "35_35") (pintype "passive"))
      (node (ref "J2") (pin "37") (pinfunction "37_37") (pintype "passive"))
      (node (ref "J2") (pin "39") (pinfunction "39_39") (pintype "passive"))
      (node (ref "J3") (pin "8") (pinfunction "8_8") (pintype "passive"))
      (node (ref "J4") (pin "8") (pinfunction "8_8") (pintype "passive"))
      (node (ref "R1") (pin "1") (pinfunction "1_1") (pintype "passive"))
      (node (ref "R17") (pin "1") (pinfunction "1_1") (pintype "passive"))
      (node (ref "R18") (pin "1") (pinfunction "1_1") (pintype "passive"))
      (node (ref "R19") (pin "1") (pinfunction "1_1") (pintype "passive"))
      (node (ref "R2") (pin "1") (pinfunction "1_1") (pintype "passive"))
      (node (ref "R20") (pin "1") (pinfunction "1_1") (pintype "passive"))
      (node (ref "R21") (pin "1") (pinfunction "1_1") (pintype "passive"))
      (node (ref "R22") (pin "1") (pinfunction "1_1") (pintype "passive"))
      (node (ref "R23") (pin "1") (pinfunction "1_1") (pintype "passive"))
      (node (ref "R24") (pin "1") (pinfunction "1_1") (pintype "passive"))
      (node (ref "R27") (pin "1") (pinfunction "1_1") (pintype "passive"))
      (node (ref "R3") (pin "1") (pinfunction "1_1") (pintype "passive"))
      (node (ref "R30") (pin "1") (pinfunction "1_1") (pintype "passive"))
      (node (ref "R4") (pin "1") (pinfunction "1_1") (pintype "passive"))
    )
    (net (code "33") (name "KEYSTB") (class "Default")
      (node (ref "E24") (pin "1") (pinfunction "I_1") (pintype "input"))
      (node (ref "E8") (pin "5") (pinfunction "I1_5") (pintype "input"))
      (node (ref "J4") (pin "2") (pinfunction "2_2") (pintype "passive"))
    )
    (net (code "34") (name "LDSR") (class "Default")
      (node (ref "E33") (pin "13") (pinfunction "O_13") (pintype "output"))
      (node (ref "E5") (pin "9") (pinfunction "CLK_9") (pintype "input"))
      (node (ref "E6") (pin "9") (pinfunction "CLK_9") (pintype "input"))
      (node (ref "E7") (pin "9") (pinfunction "CLK_9") (pintype "input"))
    )
    (net (code "35") (name "MH0") (class "Default")
      (node (ref "E20") (pin "9") (pinfunction "Q_9") (pintype "output"))
      (node (ref "E22") (pin "11") (pinfunction "I0_11") (pintype "input"))
      (node (ref "E8") (pin "13") (pinfunction "I1_13") (pintype "input"))
    )
    (net (code "36") (name "MPXA") (class "Default")
      (node (ref "E17") (pin "14") (pinfunction "A_14") (pintype "input"))
      (node (ref "E18") (pin "14") (pinfunction "A_14") (pintype "input"))
      (node (ref "E19") (pin "14") (pinfunction "A_14") (pintype "input"))
      (node (ref "J4") (pin "14") (pinfunction "14_14") (pintype "passive"))
    )
    (net (code "37") (name "MPXB") (class "Default")
      (node (ref "E17") (pin "2") (pinfunction "B_2") (pintype "input"))
      (node (ref "E18") (pin "2") (pinfunction "B_2") (pintype "input"))
      (node (ref "E19") (pin "2") (pinfunction "B_2") (pintype "input"))
      (node (ref "J4") (pin "13") (pinfunction "13_13") (pintype "passive"))
    )
    (net (code "38") (name "NUM") (class "Default")
      (node (ref "E16") (pin "12") (pinfunction "D_12") (pintype "input"))
      (node (ref "E21") (pin "13") (pinfunction "I2_13") (pintype "input"))
      (node (ref "E8") (pin "4") (pinfunction "I0_4") (pintype "input"))
      (node (ref "J4") (pin "11") (pinfunction "11_11") (pintype "passive"))
    )
    (net (code "39") (name "NUMCLK") (class "Default")
      (node (ref "E1") (pin "8") (pinfunction "CK2_8") (pintype "input"))
      (node (ref "E1") (pin "9") (pinfunction "CK1_9") (pintype "input"))
      (node (ref "E2") (pin "8") (pinfunction "CK2_8") (pintype "input"))
      (node (ref "E2") (pin "9") (pinfunction "CK1_9") (pintype "input"))
      (node (ref "E3") (pin "8") (pinfunction "CK2_8") (pintype "input"))
      (node (ref "E3") (pin "9") (pinfunction "CK1_9") (pintype "input"))
      (node (ref "E8") (pin "6") (pinfunction "O_6") (pintype "output"))
    )
    (net (code "40") (name "Net-(E1A-QB)") (class "Default")
      (node (ref "E1") (pin "12") (pinfunction "QB_12") (pintype "output"))
      (node (ref "E5") (pin "12") (pinfunction "D3_12") (pintype "input"))
      (node (ref "E9") (pin "6") (pinfunction "A3_6") (pintype "input"))
    )
    (net (code "41") (name "Net-(E1A-QC)") (class "Default")
      (node (ref "E1") (pin "11") (pinfunction "QC_11") (pintype "output"))
      (node (ref "E5") (pin "5") (pinfunction "D2_5") (pintype "input"))
      (node (ref "E9") (pin "4") (pinfunction "A2_4") (pintype "input"))
    )
    (net (code "42") (name "Net-(E1A-QD)") (class "Default")
      (node (ref "E1") (pin "10") (pinfunction "QD_10") (pintype "output"))
      (node (ref "E5") (pin "4") (pinfunction "D1_4") (pintype "input"))
      (node (ref "E9") (pin "2") (pinfunction "A1_2") (pintype "input"))
    )
    (net (code "43") (name "Net-(E4B-C)") (class "Default")
      (node (ref "C37") (pin "2") (pinfunction "2_2") (pintype "passive"))
      (node (ref "C40") (pin "2") (pinfunction "2_2") (pintype "passive"))
      (node (ref "E4") (pin "6") (pinfunction "C_6") (pintype "input"))
    )
    (net (code "44") (name "Net-(E4B-Q)") (class "Default")
      (node (ref "E4") (pin "5") (pinfunction "Q_5") (pintype "output"))
      (node (ref "E8") (pin "10") (pinfunction "I1_10") (pintype "input"))
      (node (ref "E8") (pin "12") (pinfunction "I0_12") (pintype "input"))
    )
    (net (code "45") (name "Net-(E4B-R{slash}C)") (class "Default")
      (node (ref "C37") (pin "1") (pinfunction "1_1") (pintype "passive"))
      (node (ref "C40") (pin "1") (pinfunction "1_1") (pintype "passive"))
      (node (ref "E4") (pin "7") (pinfunction "R/C_7") (pintype "input"))
      (node (ref "R25") (pin "2") (pinfunction "2_2") (pintype "passive"))
    )
    (net (code "46") (name "Net-(E5A-Q1)") (class "Default")
      (node (ref "E5") (pin "2") (pinfunction "Q1_2") (pintype "output"))
      (node (ref "E9") (pin "17") (pinfunction "A4_17") (pintype "input"))
    )
    (net (code "47") (name "Net-(E5A-Q2)") (class "Default")
      (node (ref "E5") (pin "7") (pinfunction "Q2_7") (pintype "output"))
      (node (ref "E9") (pin "15") (pinfunction "A3_15") (pintype "input"))
    )
    (net (code "48") (name "Net-(E5A-Q3)") (class "Default")
      (node (ref "E5") (pin "10") (pinfunction "Q3_10") (pintype "output"))
      (node (ref "E9") (pin "13") (pinfunction "A2_13") (pintype "input"))
    )
    (net (code "49") (name "Net-(E5A-Q4)") (class "Default")
      (node (ref "E5") (pin "15") (pinfunction "Q4_15") (pintype "output"))
      (node (ref "E9") (pin "11") (pinfunction "A1_11") (pintype "input"))
    )
    (net (code "50") (name "Net-(E10A-A1)") (class "Default")
      (node (ref "E10") (pin "2") (pinfunction "A1_2") (pintype "input"))
      (node (ref "E2") (pin "10") (pinfunction "QD_10") (pintype "output"))
      (node (ref "E6") (pin "4") (pinfunction "D1_4") (pintype "input"))
    )
    (net (code "51") (name "Net-(E10A-A2)") (class "Default")
      (node (ref "E10") (pin "4") (pinfunction "A2_4") (pintype "input"))
      (node (ref "E2") (pin "11") (pinfunction "QC_11") (pintype "output"))
      (node (ref "E6") (pin "5") (pinfunction "D2_5") (pintype "input"))
    )
    (net (code "52") (name "Net-(E10A-A3)") (class "Default")
      (node (ref "E10") (pin "6") (pinfunction "A3_6") (pintype "input"))
      (node (ref "E2") (pin "12") (pinfunction "QB_12") (pintype "output"))
      (node (ref "E6") (pin "12") (pinfunction "D3_12") (pintype "input"))
    )
    (net (code "53") (name "Net-(E10B-A1)") (class "Default")
      (node (ref "E10") (pin "11") (pinfunction "A1_11") (pintype "input"))
      (node (ref "E6") (pin "15") (pinfunction "Q4_15") (pintype "output"))
    )
    (net (code "54") (name "Net-(E10B-A2)") (class "Default")
      (node (ref "E10") (pin "13") (pinfunction "A2_13") (pintype "input"))
      (node (ref "E6") (pin "10") (pinfunction "Q3_10") (pintype "output"))
    )
    (net (code "55") (name "Net-(E10B-A3)") (class "Default")
      (node (ref "E10") (pin "15") (pinfunction "A3_15") (pintype "input"))
      (node (ref "E6") (pin "7") (pinfunction "Q2_7") (pintype "output"))
    )
    (net (code "56") (name "Net-(E10B-A4)") (class "Default")
      (node (ref "E10") (pin "17") (pinfunction "A4_17") (pintype "input"))
      (node (ref "E6") (pin "2") (pinfunction "Q1_2") (pintype "output"))
    )
    (net (code "57") (name "Net-(E11A-A1)") (class "Default")
      (node (ref "E11") (pin "2") (pinfunction "A1_2") (pintype "input"))
      (node (ref "E3") (pin "10") (pinfunction "QD_10") (pintype "output"))
      (node (ref "E7") (pin "4") (pinfunction "D1_4") (pintype "input"))
    )
    (net (code "58") (name "Net-(E11A-A2)") (class "Default")
      (node (ref "E11") (pin "4") (pinfunction "A2_4") (pintype "input"))
      (node (ref "E3") (pin "11") (pinfunction "QC_11") (pintype "output"))
      (node (ref "E7") (pin "5") (pinfunction "D2_5") (pintype "input"))
    )
    (net (code "59") (name "Net-(E11A-A3)") (class "Default")
      (node (ref "E11") (pin "6") (pinfunction "A3_6") (pintype "input"))
      (node (ref "E3") (pin "12") (pinfunction "QB_12") (pintype "output"))
      (node (ref "E7") (pin "12") (pinfunction "D3_12") (pintype "input"))
    )
    (net (code "60") (name "Net-(E11B-A1)") (class "Default")
      (node (ref "E11") (pin "11") (pinfunction "A1_11") (pintype "input"))
      (node (ref "E7") (pin "15") (pinfunction "Q4_15") (pintype "output"))
    )
    (net (code "61") (name "Net-(E11B-A2)") (class "Default")
      (node (ref "E11") (pin "13") (pinfunction "A2_13") (pintype "input"))
      (node (ref "E7") (pin "10") (pinfunction "Q3_10") (pintype "output"))
    )
    (net (code "62") (name "Net-(E11B-A3)") (class "Default")
      (node (ref "E11") (pin "15") (pinfunction "A3_15") (pintype "input"))
      (node (ref "E7") (pin "7") (pinfunction "Q2_7") (pintype "output"))
    )
    (net (code "63") (name "Net-(E11B-A4)") (class "Default")
      (node (ref "E11") (pin "17") (pinfunction "A4_17") (pintype "input"))
      (node (ref "E7") (pin "2") (pinfunction "Q1_2") (pintype "output"))
    )
    (net (code "64") (name "Net-(E12A-Q1)") (class "Default")
      (node (ref "E12") (pin "2") (pinfunction "Q1_2") (pintype "output"))
      (node (ref "E17") (pin "4") (pinfunction "1C2_4") (pintype "input"))
    )
    (net (code "65") (name "Net-(E12A-Q2)") (class "Default")
      (node (ref "E12") (pin "5") (pinfunction "Q2_5") (pintype "output"))
      (node (ref "E17") (pin "6") (pinfunction "1C0_6") (pintype "input"))
    )
    (net (code "66") (name "Net-(E12A-Q3)") (class "Default")
      (node (ref "E12") (pin "7") (pinfunction "Q3_7") (pintype "output"))
      (node (ref "E17") (pin "13") (pinfunction "2C3_13") (pintype "input"))
    )
    (net (code "67") (name "Net-(E12A-Q4)") (class "Default")
      (node (ref "E12") (pin "10") (pinfunction "Q4_10") (pintype "output"))
      (node (ref "E17") (pin "11") (pinfunction "2C1_11") (pintype "input"))
    )
    (net (code "68") (name "Net-(E12A-Q5)") (class "Default")
      (node (ref "E12") (pin "12") (pinfunction "Q5_12") (pintype "output"))
      (node (ref "E17") (pin "12") (pinfunction "2C2_12") (pintype "input"))
    )
    (net (code "69") (name "Net-(E12A-Q6)") (class "Default")
      (node (ref "E12") (pin "15") (pinfunction "Q6_15") (pintype "output"))
      (node (ref "E17") (pin "10") (pinfunction "2C0_10") (pintype "input"))
    )
    (net (code "70") (name "Net-(E13A-Q1)") (class "Default")
      (node (ref "E13") (pin "2") (pinfunction "Q1_2") (pintype "output"))
      (node (ref "E19") (pin "12") (pinfunction "2C2_12") (pintype "input"))
    )
    (net (code "71") (name "Net-(E13A-Q2)") (class "Default")
      (node (ref "E13") (pin "5") (pinfunction "Q2_5") (pintype "output"))
      (node (ref "E19") (pin "10") (pinfunction "2C0_10") (pintype "input"))
    )
    (net (code "72") (name "Net-(E13A-Q3)") (class "Default")
      (node (ref "E13") (pin "7") (pinfunction "Q3_7") (pintype "output"))
      (node (ref "E18") (pin "3") (pinfunction "1C3_3") (pintype "input"))
    )
    (net (code "73") (name "Net-(E13A-Q4)") (class "Default")
      (node (ref "E13") (pin "10") (pinfunction "Q4_10") (pintype "output"))
      (node (ref "E18") (pin "5") (pinfunction "1C1_5") (pintype "input"))
    )
    (net (code "74") (name "Net-(E13A-Q5)") (class "Default")
      (node (ref "E13") (pin "12") (pinfunction "Q5_12") (pintype "output"))
      (node (ref "E18") (pin "4") (pinfunction "1C2_4") (pintype "input"))
    )
    (net (code "75") (name "Net-(E13A-Q6)") (class "Default")
      (node (ref "E13") (pin "15") (pinfunction "Q6_15") (pintype "output"))
      (node (ref "E18") (pin "6") (pinfunction "1C0_6") (pintype "input"))
    )
    (net (code "76") (name "Net-(E14A-Q1)") (class "Default")
      (node (ref "E14") (pin "2") (pinfunction "Q1_2") (pintype "output"))
      (node (ref "E18") (pin "13") (pinfunction "2C3_13") (pintype "input"))
    )
    (net (code "77") (name "Net-(E14A-Q2)") (class "Default")
      (node (ref "E14") (pin "5") (pinfunction "Q2_5") (pintype "output"))
      (node (ref "E18") (pin "11") (pinfunction "2C1_11") (pintype "input"))
    )
    (net (code "78") (name "Net-(E14A-Q3)") (class "Default")
      (node (ref "E14") (pin "7") (pinfunction "Q3_7") (pintype "output"))
      (node (ref "E18") (pin "12") (pinfunction "2C2_12") (pintype "input"))
    )
    (net (code "79") (name "Net-(E14A-Q4)") (class "Default")
      (node (ref "E14") (pin "10") (pinfunction "Q4_10") (pintype "output"))
      (node (ref "E18") (pin "10") (pinfunction "2C0_10") (pintype "input"))
    )
    (net (code "80") (name "Net-(E14A-Q5)") (class "Default")
      (node (ref "E14") (pin "12") (pinfunction "Q5_12") (pintype "output"))
      (node (ref "E17") (pin "3") (pinfunction "1C3_3") (pintype "input"))
    )
    (net (code "81") (name "Net-(E14A-Q6)") (class "Default")
      (node (ref "E14") (pin "15") (pinfunction "Q6_15") (pintype "output"))
      (node (ref "E17") (pin "5") (pinfunction "1C1_5") (pintype "input"))
    )
    (net (code "82") (name "Net-(E15A-Q1)") (class "Default")
      (node (ref "E15") (pin "2") (pinfunction "Q1_2") (pintype "output"))
      (node (ref "E19") (pin "3") (pinfunction "1C3_3") (pintype "input"))
    )
    (net (code "83") (name "Net-(E15A-Q2)") (class "Default")
      (node (ref "E15") (pin "5") (pinfunction "Q2_5") (pintype "output"))
      (node (ref "E19") (pin "5") (pinfunction "1C1_5") (pintype "input"))
    )
    (net (code "84") (name "Net-(E15A-Q3)") (class "Default")
      (node (ref "E15") (pin "7") (pinfunction "Q3_7") (pintype "output"))
      (node (ref "E19") (pin "4") (pinfunction "1C2_4") (pintype "input"))
    )
    (net (code "85") (name "Net-(E15A-Q4)") (class "Default")
      (node (ref "E15") (pin "10") (pinfunction "Q4_10") (pintype "output"))
      (node (ref "E19") (pin "6") (pinfunction "1C0_6") (pintype "input"))
    )
    (net (code "86") (name "Net-(E15A-Q5)") (class "Default")
      (node (ref "E15") (pin "12") (pinfunction "Q5_12") (pintype "output"))
      (node (ref "E19") (pin "13") (pinfunction "2C3_13") (pintype "input"))
    )
    (net (code "87") (name "Net-(E15A-Q6)") (class "Default")
      (node (ref "E15") (pin "15") (pinfunction "Q6_15") (pintype "output"))
      (node (ref "E19") (pin "11") (pinfunction "2C1_11") (pintype "input"))
    )
    (net (code "88") (name "Net-(E16A-CLK)") (class "Default")
      (node (ref "E16") (pin "3") (pinfunction "CLK_3") (pintype "input"))
      (node (ref "E21") (pin "12") (pinfunction "O_12") (pintype "output"))
    )
    (net (code "89") (name "Net-(E20A-PRE)") (class "Default")
      (node (ref "E20") (pin "4") (pinfunction "PRE_4") (pintype "input"))
      (node (ref "E26") (pin "8") (pinfunction "~{Q4}_8") (pintype "output"))
    )
    (net (code "90") (name "Net-(E20B-CLK)") (class "Default")
      (node (ref "E20") (pin "11") (pinfunction "CLK_11") (pintype "input"))
      (node (ref "E22") (pin "1") (pinfunction "O_1") (pintype "output"))
      (node (ref "E4") (pin "9") (pinfunction "A_9") (pintype "input"))
    )
    (net (code "91") (name "Net-(E21A-I0)") (class "Default")
      (node (ref "E21") (pin "1") (pinfunction "I0_1") (pintype "input"))
      (node (ref "E24") (pin "4") (pinfunction "O_4") (pintype "output"))
    )
    (net (code "92") (name "Net-(E21B-I0)") (class "Default")
      (node (ref "E21") (pin "3") (pinfunction "I0_3") (pintype "input"))
      (node (ref "E21") (pin "4") (pinfunction "I1_4") (pintype "input"))
      (node (ref "E22") (pin "4") (pinfunction "O_4") (pintype "output"))
    )
    (net (code "93") (name "Net-(E21C-O)") (class "Default")
      (node (ref "E21") (pin "8") (pinfunction "O_8") (pintype "output"))
      (node (ref "E23") (pin "9") (pinfunction "I_9") (pintype "input"))
    )
    (net (code "94") (name "Net-(E22A-I0)") (class "Default")
      (node (ref "E22") (pin "2") (pinfunction "I0_2") (pintype "input"))
      (node (ref "E32") (pin "6") (pinfunction "O_6") (pintype "output"))
    )
    (net (code "95") (name "Net-(E22A-I1)") (class "Default")
      (node (ref "E22") (pin "3") (pinfunction "I1_3") (pintype "input"))
      (node (ref "E33") (pin "1") (pinfunction "O_1") (pintype "output"))
    )
    (net (code "96") (name "Net-(E22B-I0)") (class "Default")
      (node (ref "E22") (pin "5") (pinfunction "I0_5") (pintype "input"))
      (node (ref "E8") (pin "3") (pinfunction "O_3") (pintype "output"))
    )
    (net (code "97") (name "Net-(E22C-I0)") (class "Default")
      (node (ref "E22") (pin "8") (pinfunction "I0_8") (pintype "input"))
      (node (ref "E25") (pin "12") (pinfunction "O_12") (pintype "output"))
    )
    (net (code "98") (name "Net-(E22C-I1)") (class "Default")
      (node (ref "E22") (pin "9") (pinfunction "I1_9") (pintype "input"))
      (node (ref "E25") (pin "8") (pinfunction "O_8") (pintype "output"))
    )
    (net (code "99") (name "Net-(E22C-O)") (class "Default")
      (node (ref "E22") (pin "10") (pinfunction "O_10") (pintype "output"))
      (node (ref "E29") (pin "4") (pinfunction "G2A_4") (pintype "input"))
      (node (ref "E29") (pin "5") (pinfunction "G2B_5") (pintype "input"))
      (node (ref "E31") (pin "15") (pinfunction "2G_15") (pintype "input"))
    )
    (net (code "100") (name "Net-(E22D-O)") (class "Default")
      (node (ref "E22") (pin "13") (pinfunction "O_13") (pintype "output"))
      (node (ref "E30") (pin "4") (pinfunction "I0_4") (pintype "input"))
    )
    (net (code "101") (name "Net-(E23A-I)") (class "Default")
      (node (ref "E23") (pin "1") (pinfunction "I_1") (pintype "input"))
      (node (ref "E33") (pin "4") (pinfunction "O_4") (pintype "output"))
    )
    (net (code "102") (name "Net-(E23E-I)") (class "Default")
      (node (ref "E23") (pin "11") (pinfunction "I_11") (pintype "input"))
      (node (ref "E24") (pin "10") (pinfunction "O_10") (pintype "output"))
    )
    (net (code "103") (name "Net-(E23F-I)") (class "Default")
      (node (ref "E23") (pin "13") (pinfunction "I_13") (pintype "input"))
      (node (ref "E25") (pin "6") (pinfunction "O_6") (pintype "output"))
    )
    (net (code "104") (name "Net-(E24D-O)") (class "Default")
      (node (ref "E24") (pin "8") (pinfunction "O_8") (pintype "output"))
      (node (ref "E32") (pin "5") (pinfunction "I1_5") (pintype "input"))
    )
    (net (code "105") (name "Net-(E24F-O)") (class "Default")
      (node (ref "E24") (pin "12") (pinfunction "O_12") (pintype "output"))
      (node (ref "E25") (pin "10") (pinfunction "I1_10") (pintype "input"))
      (node (ref "E28") (pin "1") (pinfunction "1G_1") (pintype "input"))
      (node (ref "E28") (pin "15") (pinfunction "2G_15") (pintype "input"))
      (node (ref "E33") (pin "6") (pinfunction "I1_6") (pintype "input"))
    )
    (net (code "106") (name "Net-(E25A-I0)") (class "Default")
      (node (ref "E25") (pin "1") (pinfunction "I0_1") (pintype "input"))
      (node (ref "E26") (pin "16") (pinfunction "Q1_16") (pintype "output"))
      (node (ref "E29") (pin "3") (pinfunction "C_3") (pintype "input"))
    )
    (net (code "107") (name "Net-(E25A-I2)") (class "Default")
      (node (ref "E25") (pin "13") (pinfunction "I2_13") (pintype "input"))
      (node (ref "E26") (pin "15") (pinfunction "Q2_15") (pintype "output"))
      (node (ref "E27") (pin "3") (pinfunction "I_3") (pintype "input"))
      (node (ref "E29") (pin "2") (pinfunction "B_2") (pintype "input"))
      (node (ref "E30") (pin "1") (pinfunction "I0_1") (pintype "input"))
    )
    (net (code "108") (name "Net-(E25B-I2)") (class "Default")
      (node (ref "D1") (pin "A") (pinfunction "A_A") (pintype "passive"))
      (node (ref "D2") (pin "A") (pinfunction "A_A") (pintype "passive"))
      (node (ref "E25") (pin "5") (pinfunction "I2_5") (pintype "input"))
      (node (ref "R37") (pin "1") (pinfunction "1_1") (pintype "passive"))
    )
    (net (code "109") (name "Net-(E25C-I0)") (class "Default")
      (node (ref "E25") (pin "9") (pinfunction "I0_9") (pintype "input"))
      (node (ref "E26") (pin "9") (pinfunction "Q4_9") (pintype "output"))
    )
    (net (code "110") (name "Net-(E26A-Q3)") (class "Default")
      (node (ref "E26") (pin "10") (pinfunction "Q3_10") (pintype "output"))
      (node (ref "E29") (pin "1") (pinfunction "A_1") (pintype "input"))
    )
    (net (code "111") (name "Net-(E27A-O)") (class "Default")
      (node (ref "E27") (pin "2") (pinfunction "O_2") (pintype "output"))
      (node (ref "E30") (pin "12") (pinfunction "I0_12") (pintype "input"))
    )
    (net (code "112") (name "Net-(E27B-O)") (class "Default")
      (node (ref "E27") (pin "4") (pinfunction "O_4") (pintype "output"))
      (node (ref "E31") (pin "12") (pinfunction "2A1_12") (pintype "input"))
    )
    (net (code "113") (name "Net-(E27C-O)") (class "Default")
      (node (ref "E27") (pin "6") (pinfunction "O_6") (pintype "output"))
      (node (ref "E30") (pin "13") (pinfunction "I1_13") (pintype "input"))
    )
    (net (code "114") (name "Net-(E28A-1A1)") (class "Default")
      (node (ref "E28") (pin "2") (pinfunction "1A1_2") (pintype "input"))
      (node (ref "E29") (pin "9") (pinfunction "Y6_9") (pintype "output"))
      (node (ref "E32") (pin "2") (pinfunction "I1_2") (pintype "input"))
    )
    (net (code "115") (name "Net-(E28A-1A2)") (class "Default")
      (node (ref "E28") (pin "4") (pinfunction "1A2_4") (pintype "input"))
      (node (ref "E29") (pin "7") (pinfunction "Y7_7") (pintype "output"))
      (node (ref "E30") (pin "10") (pinfunction "I1_10") (pintype "input"))
      (node (ref "E32") (pin "1") (pinfunction "I0_1") (pintype "input"))
    )
    (net (code "116") (name "Net-(E28A-1A3)") (class "Default")
      (node (ref "E28") (pin "6") (pinfunction "1A3_6") (pintype "input"))
      (node (ref "E30") (pin "9") (pinfunction "I0_9") (pintype "input"))
      (node (ref "E31") (pin "6") (pinfunction "1A3_6") (pintype "input"))
      (node (ref "E32") (pin "8") (pinfunction "O_8") (pintype "output"))
      (node (ref "E33") (pin "5") (pinfunction "I0_5") (pintype "input"))
    )
    (net (code "117") (name "Net-(E28A-2A2)") (class "Default")
      (node (ref "E28") (pin "14") (pinfunction "2A2_14") (pintype "input"))
      (node (ref "E30") (pin "11") (pinfunction "O_11") (pintype "output"))
    )
    (net (code "118") (name "Net-(E29A-Y0)") (class "Default")
      (node (ref "E29") (pin "15") (pinfunction "Y0_15") (pintype "output"))
      (node (ref "E33") (pin "8") (pinfunction "I0_8") (pintype "input"))
    )
    (net (code "119") (name "Net-(E29A-Y1)") (class "Default")
      (node (ref "E29") (pin "14") (pinfunction "Y1_14") (pintype "output"))
      (node (ref "E33") (pin "12") (pinfunction "I1_12") (pintype "input"))
    )
    (net (code "120") (name "Net-(E29A-Y2)") (class "Default")
      (node (ref "E29") (pin "13") (pinfunction "Y2_13") (pintype "output"))
      (node (ref "E30") (pin "2") (pinfunction "I1_2") (pintype "input"))
      (node (ref "E32") (pin "10") (pinfunction "I1_10") (pintype "input"))
    )
    (net (code "121") (name "Net-(E29A-Y3)") (class "Default")
      (node (ref "E29") (pin "12") (pinfunction "Y3_12") (pintype "output"))
      (node (ref "E32") (pin "9") (pinfunction "I0_9") (pintype "input"))
    )
    (net (code "122") (name "Net-(E29A-Y4)") (class "Default")
      (node (ref "E29") (pin "11") (pinfunction "Y4_11") (pintype "output"))
      (node (ref "E31") (pin "10") (pinfunction "1A4_10") (pintype "input"))
    )
    (net (code "123") (name "Net-(E29A-Y5)") (class "Default")
      (node (ref "E29") (pin "10") (pinfunction "Y5_10") (pintype "output"))
      (node (ref "E31") (pin "2") (pinfunction "1A1_2") (pintype "input"))
    )
    (net (code "124") (name "Net-(E30A-O)") (class "Default")
      (node (ref "E30") (pin "3") (pinfunction "O_3") (pintype "output"))
      (node (ref "E31") (pin "14") (pinfunction "2A2_14") (pintype "input"))
    )
    (net (code "125") (name "Net-(E30B-O)") (class "Default")
      (node (ref "E30") (pin "6") (pinfunction "O_6") (pintype "output"))
      (node (ref "E34") (pin "1") (pinfunction "1G_1") (pintype "input"))
      (node (ref "E34") (pin "15") (pinfunction "2G_15") (pintype "input"))
      (node (ref "E35") (pin "4") (pinfunction "G2A_4") (pintype "input"))
      (node (ref "E35") (pin "5") (pinfunction "G2B_5") (pintype "input"))
    )
    (net (code "126") (name "Net-(E31A-1A2)") (class "Default")
      (node (ref "E31") (pin "4") (pinfunction "1A2_4") (pintype "input"))
      (node (ref "E32") (pin "3") (pinfunction "O_3") (pintype "output"))
    )
    (net (code "127") (name "Net-(E31A-1Y1)") (class "Default")
      (node (ref "D2") (pin "C") (pinfunction "C_C") (pintype "passive"))
      (node (ref "E31") (pin "3") (pinfunction "1Y1_3") (pintype "tri_state"))
    )
    (net (code "128") (name "Net-(E31A-1Y2)") (class "Default")
      (node (ref "D1") (pin "C") (pinfunction "C_C") (pintype "passive"))
      (node (ref "E31") (pin "5") (pinfunction "1Y2_5") (pintype "tri_state"))
    )
    (net (code "129") (name "Net-(E32D-I0)") (class "Default")
      (node (ref "E32") (pin "12") (pinfunction "I0_12") (pintype "input"))
      (node (ref "E35") (pin "11") (pinfunction "Y4_11") (pintype "output"))
    )
    (net (code "130") (name "Net-(E33C-O)") (class "Default")
      (node (ref "E33") (pin "10") (pinfunction "O_10") (pintype "output"))
      (node (ref "E36") (pin "9") (pinfunction "CLK_9") (pintype "input"))
    )
    (net (code "131") (name "Net-(E34A-1A3)") (class "Default")
      (node (ref "E34") (pin "6") (pinfunction "1A3_6") (pintype "input"))
      (node (ref "E35") (pin "9") (pinfunction "Y6_9") (pintype "output"))
    )
    (net (code "132") (name "Net-(E34A-2A1)") (class "Default")
      (node (ref "E34") (pin "12") (pinfunction "2A1_12") (pintype "input"))
      (node (ref "E35") (pin "10") (pinfunction "Y5_10") (pintype "output"))
    )
    (net (code "133") (name "POWCK") (class "Default")
      (node (ref "E24") (pin "11") (pinfunction "I_11") (pintype "input"))
      (node (ref "J2") (pin "28") (pinfunction "28_28") (pintype "passive"))
      (node (ref "R33") (pin "1") (pinfunction "1_1") (pintype "passive"))
    )
    (net (code "134") (name "THIS") (class "Default")
      (node (ref "E20") (pin "5") (pinfunction "Q_5") (pintype "output"))
      (node (ref "E28") (pin "12") (pinfunction "2A1_12") (pintype "input"))
    )
    (net (code "135") (name "VCC") (class "Default")
      (node (ref "C1") (pin "1") (pinfunction "1_1") (pintype "passive"))
      (node (ref "C10") (pin "1") (pinfunction "1_1") (pintype "passive"))
      (node (ref "C11") (pin "1") (pinfunction "1_1") (pintype "passive"))
      (node (ref "C12") (pin "1") (pinfunction "1_1") (pintype "passive"))
      (node (ref "C13") (pin "1") (pinfunction "1_1") (pintype "passive"))
      (node (ref "C14") (pin "1") (pinfunction "1_1") (pintype "passive"))
      (node (ref "C15") (pin "1") (pinfunction "1_1") (pintype "passive"))
      (node (ref "C16") (pin "1") (pinfunction "1_1") (pintype "passive"))
      (node (ref "C17") (pin "1") (pinfunction "1_1") (pintype "passive"))
      (node (ref "C18") (pin "1") (pinfunction "1_1") (pintype "passive"))
      (node (ref "C19") (pin "1") (pinfunction "1_1") (pintype "passive"))
      (node (ref "C2") (pin "1") (pinfunction "1_1") (pintype "passive"))
      (node (ref "C20") (pin "1") (pinfunction "1_1") (pintype "passive"))
      (node (ref "C21") (pin "1") (pinfunction "1_1") (pintype "passive"))
      (node (ref "C22") (pin "1") (pinfunction "1_1") (pintype "passive"))
      (node (ref "C23") (pin "1") (pinfunction "1_1") (pintype "passive"))
      (node (ref "C24") (pin "1") (pinfunction "1_1") (pintype "passive"))
      (node (ref "C25") (pin "1") (pinfunction "1_1") (pintype "passive"))
      (node (ref "C26") (pin "1") (pinfunction "1_1") (pintype "passive"))
      (node (ref "C27") (pin "1") (pinfunction "1_1") (pintype "passive"))
      (node (ref "C28") (pin "1") (pinfunction "1_1") (pintype "passive"))
      (node (ref "C29") (pin "1") (pinfunction "1_1") (pintype "passive"))
      (node (ref "C3") (pin "1") (pinfunction "1_1") (pintype "passive"))
      (node (ref "C30") (pin "1") (pinfunction "1_1") (pintype "passive"))
      (node (ref "C31") (pin "1") (pinfunction "1_1") (pintype "passive"))
      (node (ref "C32") (pin "1") (pinfunction "1_1") (pintype "passive"))
      (node (ref "C33") (pin "1") (pinfunction "1_1") (pintype "passive"))
      (node (ref "C34") (pin "1") (pinfunction "1_1") (pintype "passive"))
      (node (ref "C35") (pin "1") (pinfunction "1_1") (pintype "passive"))
      (node (ref "C36") (pin "1") (pinfunction "1_1") (pintype "passive"))
      (node (ref "C38") (pin "+") (pinfunction "+_+") (pintype "passive"))
      (node (ref "C39") (pin "+") (pinfunction "+_+") (pintype "passive"))
      (node (ref "C4") (pin "1") (pinfunction "1_1") (pintype "passive"))
      (node (ref "C5") (pin "1") (pinfunction "1_1") (pintype "passive"))
      (node (ref "C6") (pin "1") (pinfunction "1_1") (pintype "passive"))
      (node (ref "C7") (pin "1") (pinfunction "1_1") (pintype "passive"))
      (node (ref "C8") (pin "1") (pinfunction "1_1") (pintype "passive"))
      (node (ref "C9") (pin "1") (pinfunction "1_1") (pintype "passive"))
      (node (ref "E16") (pin "10") (pinfunction "PRE_10") (pintype "input"))
      (node (ref "E16") (pin "4") (pinfunction "PRE_4") (pintype "input"))
      (node (ref "E20") (pin "10") (pinfunction "PRE_10") (pintype "input"))
      (node (ref "E29") (pin "6") (pinfunction "G1_6") (pintype "input"))
      (node (ref "E34") (pin "10") (pinfunction "1A4_10") (pintype "input"))
      (node (ref "E35") (pin "6") (pinfunction "G1_6") (pintype "input"))
      (node (ref "E36") (pin "1") (pinfunction "CLR_1") (pintype "input"))
      (node (ref "E36") (pin "11") (pinfunction "D4_11") (pintype "input"))
      (node (ref "E36") (pin "13") (pinfunction "D5_13") (pintype "input"))
      (node (ref "E36") (pin "6") (pinfunction "D3_6") (pintype "input"))
      (node (ref "E4") (pin "10") (pinfunction "B_10") (pintype "input"))
      (node (ref "E4") (pin "11") (pinfunction "CLR_11") (pintype "input"))
      (node (ref "J1") (pin "1") (pinfunction "1_1") (pintype "passive"))
      (node (ref "J1") (pin "2") (pinfunction "2_2") (pintype "passive"))
      (node (ref "J1") (pin "3") (pinfunction "3_3") (pintype "passive"))
      (node (ref "J1") (pin "4") (pinfunction "4_4") (pintype "passive"))
      (node (ref "J1") (pin "5") (pinfunction "5_5") (pintype "passive"))
      (node (ref "J1") (pin "7") (pinfunction "7_7") (pintype "passive"))
      (node (ref "J1") (pin "9") (pinfunction "9_9") (pintype "passive"))
      (node (ref "J2") (pin "1") (pinfunction "1_1") (pintype "passive"))
      (node (ref "J2") (pin "3") (pinfunction "3_3") (pintype "passive"))
      (node (ref "J2") (pin "5") (pinfunction "5_5") (pintype "passive"))
      (node (ref "J2") (pin "7") (pinfunction "7_7") (pintype "passive"))
      (node (ref "J2") (pin "9") (pinfunction "9_9") (pintype "passive"))
      (node (ref "J3") (pin "16") (pinfunction "16_16") (pintype "passive"))
      (node (ref "J4") (pin "16") (pinfunction "16_16") (pintype "passive"))
      (node (ref "R10") (pin "2") (pinfunction "2_2") (pintype "passive"))
      (node (ref "R11") (pin "2") (pinfunction "2_2") (pintype "passive"))
      (node (ref "R12") (pin "2") (pinfunction "2_2") (pintype "passive"))
      (node (ref "R13") (pin "2") (pinfunction "2_2") (pintype "passive"))
      (node (ref "R14") (pin "2") (pinfunction "2_2") (pintype "passive"))
      (node (ref "R15") (pin "2") (pinfunction "2_2") (pintype "passive"))
      (node (ref "R16") (pin "2") (pinfunction "2_2") (pintype "passive"))
      (node (ref "R25") (pin "1") (pinfunction "1_1") (pintype "passive"))
      (node (ref "R26") (pin "2") (pinfunction "2_2") (pintype "passive"))
      (node (ref "R28") (pin "2") (pinfunction "2_2") (pintype "passive"))
      (node (ref "R29") (pin "2") (pinfunction "2_2") (pintype "passive"))
      (node (ref "R31") (pin "2") (pinfunction "2_2") (pintype "passive"))
      (node (ref "R32") (pin "2") (pinfunction "2_2") (pintype "passive"))
      (node (ref "R33") (pin "2") (pinfunction "2_2") (pintype "passive"))
      (node (ref "R34") (pin "1") (pinfunction "1_1") (pintype "passive"))
      (node (ref "R35") (pin "1") (pinfunction "1_1") (pintype "passive"))
      (node (ref "R36") (pin "1") (pinfunction "1_1") (pintype "passive"))
      (node (ref "R37") (pin "2") (pinfunction "2_2") (pintype "passive"))
      (node (ref "R5") (pin "2") (pinfunction "2_2") (pintype "passive"))
      (node (ref "R6") (pin "2") (pinfunction "2_2") (pintype "passive"))
      (node (ref "R7") (pin "2") (pinfunction "2_2") (pintype "passive"))
      (node (ref "R8") (pin "2") (pinfunction "2_2") (pintype "passive"))
      (node (ref "R9") (pin "2") (pinfunction "2_2") (pintype "passive"))
      (node (ref "VCC") (pin "1") (pinfunction "P_1") (pintype "passive"))
    )
    (net (code "136") (name "unconnected-(E4B-~{Q}-Pad12)") (class "Default")
      (node (ref "E4") (pin "12") (pinfunction "~{Q}_12") (pintype "output"))
    )
    (net (code "137") (name "unconnected-(E5A-~{Q1}-Pad3)") (class "Default")
      (node (ref "E5") (pin "3") (pinfunction "~{Q1}_3") (pintype "output"))
    )
    (net (code "138") (name "unconnected-(E5A-~{Q2}-Pad6)") (class "Default")
      (node (ref "E5") (pin "6") (pinfunction "~{Q2}_6") (pintype "output"))
    )
    (net (code "139") (name "unconnected-(E5A-~{Q3}-Pad11)") (class "Default")
      (node (ref "E5") (pin "11") (pinfunction "~{Q3}_11") (pintype "output"))
    )
    (net (code "140") (name "unconnected-(E5A-~{Q4}-Pad14)") (class "Default")
      (node (ref "E5") (pin "14") (pinfunction "~{Q4}_14") (pintype "output"))
    )
    (net (code "141") (name "unconnected-(E6A-~{Q1}-Pad3)") (class "Default")
      (node (ref "E6") (pin "3") (pinfunction "~{Q1}_3") (pintype "output"))
    )
    (net (code "142") (name "unconnected-(E6A-~{Q2}-Pad6)") (class "Default")
      (node (ref "E6") (pin "6") (pinfunction "~{Q2}_6") (pintype "output"))
    )
    (net (code "143") (name "unconnected-(E6A-~{Q3}-Pad11)") (class "Default")
      (node (ref "E6") (pin "11") (pinfunction "~{Q3}_11") (pintype "output"))
    )
    (net (code "144") (name "unconnected-(E6A-~{Q4}-Pad14)") (class "Default")
      (node (ref "E6") (pin "14") (pinfunction "~{Q4}_14") (pintype "output"))
    )
    (net (code "145") (name "unconnected-(E7A-~{Q1}-Pad3)") (class "Default")
      (node (ref "E7") (pin "3") (pinfunction "~{Q1}_3") (pintype "output"))
    )
    (net (code "146") (name "unconnected-(E7A-~{Q2}-Pad6)") (class "Default")
      (node (ref "E7") (pin "6") (pinfunction "~{Q2}_6") (pintype "output"))
    )
    (net (code "147") (name "unconnected-(E7A-~{Q3}-Pad11)") (class "Default")
      (node (ref "E7") (pin "11") (pinfunction "~{Q3}_11") (pintype "output"))
    )
    (net (code "148") (name "unconnected-(E7A-~{Q4}-Pad14)") (class "Default")
      (node (ref "E7") (pin "14") (pinfunction "~{Q4}_14") (pintype "output"))
    )
    (net (code "149") (name "unconnected-(E16A-Q-Pad5)") (class "Default")
      (node (ref "E16") (pin "5") (pinfunction "Q_5") (pintype "output"))
    )
    (net (code "150") (name "unconnected-(E20A-~{Q}-Pad6)") (class "Default")
      (node (ref "E20") (pin "6") (pinfunction "~{Q}_6") (pintype "output"))
    )
    (net (code "151") (name "unconnected-(E26A-~{Q1}-Pad1)") (class "Default")
      (node (ref "E26") (pin "1") (pinfunction "~{Q1}_1") (pintype "output"))
    )
    (net (code "152") (name "unconnected-(E26A-~{Q2}-Pad14)") (class "Default")
      (node (ref "E26") (pin "14") (pinfunction "~{Q2}_14") (pintype "output"))
    )
    (net (code "153") (name "unconnected-(E26A-~{Q3}-Pad11)") (class "Default")
      (node (ref "E26") (pin "11") (pinfunction "~{Q3}_11") (pintype "output"))
    )
    (net (code "154") (name "unconnected-(E34A-1Y4-Pad9)") (class "Default")
      (node (ref "E34") (pin "9") (pinfunction "1Y4_9") (pintype "tri_state"))
    )
    (net (code "155") (name "unconnected-(E35A-Y0-Pad15)") (class "Default")
      (node (ref "E35") (pin "15") (pinfunction "Y0_15") (pintype "output"))
    )
    (net (code "156") (name "unconnected-(E35A-Y1-Pad14)") (class "Default")
      (node (ref "E35") (pin "14") (pinfunction "Y1_14") (pintype "output"))
    )
    (net (code "157") (name "unconnected-(E35A-Y2-Pad13)") (class "Default")
      (node (ref "E35") (pin "13") (pinfunction "Y2_13") (pintype "output"))
    )
    (net (code "158") (name "unconnected-(E35A-Y3-Pad12)") (class "Default")
      (node (ref "E35") (pin "12") (pinfunction "Y3_12") (pintype "output"))
    )
    (net (code "159") (name "unconnected-(E35A-Y7-Pad7)") (class "Default")
      (node (ref "E35") (pin "7") (pinfunction "Y7_7") (pintype "output"))
    )
    (net (code "160") (name "unconnected-(E36A-Q3-Pad7)") (class "Default")
      (node (ref "E36") (pin "7") (pinfunction "Q3_7") (pintype "output"))
    )
    (net (code "161") (name "unconnected-(E36A-Q4-Pad10)") (class "Default")
      (node (ref "E36") (pin "10") (pinfunction "Q4_10") (pintype "output"))
    )
    (net (code "162") (name "unconnected-(E36A-Q5-Pad12)") (class "Default")
      (node (ref "E36") (pin "12") (pinfunction "Q5_12") (pintype "output"))
    )
    (net (code "163") (name "~{ADRLTH}") (class "Default")
      (node (ref "E12") (pin "9") (pinfunction "CLK_9") (pintype "input"))
      (node (ref "E14") (pin "9") (pinfunction "CLK_9") (pintype "input"))
      (node (ref "E8") (pin "11") (pinfunction "O_11") (pintype "output"))
    )
    (net (code "164") (name "~{BFSW}") (class "Default")
      (node (ref "E28") (pin "9") (pinfunction "1Y4_9") (pintype "tri_state"))
      (node (ref "J2") (pin "24") (pinfunction "24_24") (pintype "passive"))
    )
    (net (code "165") (name "~{BKDTACNTL}") (class "Default")
      (node (ref "E28") (pin "3") (pinfunction "1Y1_3") (pintype "tri_state"))
      (node (ref "J2") (pin "12") (pinfunction "12_12") (pintype "passive"))
    )
    (net (code "166") (name "~{BOOTF}") (class "Default")
      (node (ref "E16") (pin "2") (pinfunction "D_2") (pintype "input"))
      (node (ref "E16") (pin "6") (pinfunction "~{Q}_6") (pintype "output"))
      (node (ref "E28") (pin "10") (pinfunction "1A4_10") (pintype "input"))
    )
    (net (code "167") (name "~{BUSEN}") (class "Default")
      (node (ref "E34") (pin "13") (pinfunction "2Y2_13") (pintype "tri_state"))
      (node (ref "J1") (pin "24") (pinfunction "24_24") (pintype "passive"))
    )
    (net (code "168") (name "~{DEP}") (class "Default")
      (node (ref "E28") (pin "5") (pinfunction "1Y2_5") (pintype "tri_state"))
      (node (ref "J2") (pin "20") (pinfunction "20_20") (pintype "passive"))
    )
    (net (code "169") (name "~{DSPLTH}") (class "Default")
      (node (ref "E13") (pin "9") (pinfunction "CLK_9") (pintype "input"))
      (node (ref "E15") (pin "9") (pinfunction "CLK_9") (pintype "input"))
      (node (ref "E8") (pin "8") (pinfunction "O_8") (pintype "output"))
    )
    (net (code "170") (name "~{EMA0}") (class "Default")
      (node (ref "E27") (pin "11") (pinfunction "I_11") (pintype "input"))
      (node (ref "J1") (pin "30") (pinfunction "30_30") (pintype "passive"))
      (node (ref "R34") (pin "2") (pinfunction "2_2") (pintype "passive"))
    )
    (net (code "171") (name "~{EMA1}") (class "Default")
      (node (ref "E27") (pin "9") (pinfunction "I_9") (pintype "input"))
      (node (ref "J1") (pin "28") (pinfunction "28_28") (pintype "passive"))
      (node (ref "R35") (pin "2") (pinfunction "2_2") (pintype "passive"))
    )
    (net (code "172") (name "~{EMA2}") (class "Default")
      (node (ref "E27") (pin "13") (pinfunction "I_13") (pintype "input"))
      (node (ref "J1") (pin "32") (pinfunction "32_32") (pintype "passive"))
      (node (ref "R36") (pin "2") (pinfunction "2_2") (pintype "passive"))
    )
    (net (code "173") (name "~{EMODE}") (class "Default")
      (node (ref "E1") (pin "6") (pinfunction "MOD_6") (pintype "input"))
      (node (ref "E16") (pin "8") (pinfunction "~{Q}_8") (pintype "output"))
      (node (ref "E2") (pin "6") (pinfunction "MOD_6") (pintype "input"))
      (node (ref "E22") (pin "6") (pinfunction "I1_6") (pintype "input"))
      (node (ref "E3") (pin "6") (pinfunction "MOD_6") (pintype "input"))
    )
    (net (code "174") (name "~{EXTPUL}") (class "Default")
      (node (ref "J4") (pin "9") (pinfunction "9_9") (pintype "passive"))
    )
    (net (code "175") (name "~{FUN}") (class "Default")
      (node (ref "E24") (pin "3") (pinfunction "I_3") (pintype "input"))
      (node (ref "E25") (pin "11") (pinfunction "I2_11") (pintype "input"))
      (node (ref "E25") (pin "2") (pinfunction "I1_2") (pintype "input"))
      (node (ref "J4") (pin "15") (pinfunction "15_15") (pintype "passive"))
    )
    (net (code "176") (name "~{GATEENT}") (class "Default")
      (node (ref "E10") (pin "1") (pinfunction "G_1") (pintype "input"))
      (node (ref "E11") (pin "1") (pinfunction "G_1") (pintype "input"))
      (node (ref "E21") (pin "6") (pinfunction "O_6") (pintype "output"))
      (node (ref "E30") (pin "5") (pinfunction "I1_5") (pintype "input"))
      (node (ref "E9") (pin "1") (pinfunction "G_1") (pintype "input"))
    )
    (net (code "177") (name "~{GATESR}") (class "Default")
      (node (ref "E10") (pin "19") (pinfunction "G_19") (pintype "input"))
      (node (ref "E11") (pin "19") (pinfunction "G_19") (pintype "input"))
      (node (ref "E32") (pin "11") (pinfunction "O_11") (pintype "output"))
      (node (ref "E9") (pin "19") (pinfunction "G_19") (pintype "input"))
    )
    (net (code "178") (name "~{IND1}") (class "Default")
      (node (ref "E28") (pin "7") (pinfunction "1Y3_7") (pintype "tri_state"))
      (node (ref "E34") (pin "3") (pinfunction "1Y1_3") (pintype "tri_state"))
      (node (ref "J2") (pin "8") (pinfunction "8_8") (pintype "passive"))
    )
    (net (code "179") (name "~{IND2}") (class "Default")
      (node (ref "E34") (pin "5") (pinfunction "1Y2_5") (pintype "tri_state"))
      (node (ref "J2") (pin "4") (pinfunction "4_4") (pintype "passive"))
    )
    (net (code "180") (name "~{INIT}") (class "Default")
      (node (ref "E31") (pin "9") (pinfunction "1Y4_9") (pintype "tri_state"))
      (node (ref "J2") (pin "34") (pinfunction "34_34") (pintype "passive"))
    )
    (net (code "181") (name "~{KEY-F}") (class "Default")
      (node (ref "E26") (pin "13") (pinfunction "C12_13") (pintype "input"))
      (node (ref "E26") (pin "4") (pinfunction "C34_4") (pintype "input"))
      (node (ref "E27") (pin "5") (pinfunction "I_5") (pintype "input"))
      (node (ref "J4") (pin "3") (pinfunction "3_3") (pintype "passive"))
    )
    (net (code "182") (name "~{KEYCNTL}") (class "Default")
      (node (ref "E31") (pin "13") (pinfunction "2Y2_13") (pintype "tri_state"))
      (node (ref "J2") (pin "10") (pinfunction "10_10") (pintype "passive"))
    )
    (net (code "183") (name "~{KEYSTB}") (class "Default")
      (node (ref "E16") (pin "11") (pinfunction "CLK_11") (pintype "input"))
      (node (ref "E21") (pin "2") (pinfunction "I1_2") (pintype "input"))
      (node (ref "E24") (pin "2") (pinfunction "O_2") (pintype "output"))
      (node (ref "E31") (pin "1") (pinfunction "1G_1") (pintype "input"))
      (node (ref "E33") (pin "11") (pinfunction "I0_11") (pintype "input"))
      (node (ref "E33") (pin "9") (pinfunction "I1_9") (pintype "input"))
    )
    (net (code "184") (name "~{KFUN0}") (class "Default")
      (node (ref "E26") (pin "2") (pinfunction "D1_2") (pintype "input"))
      (node (ref "E3") (pin "1") (pinfunction "SER_1") (pintype "input"))
      (node (ref "E3") (pin "2") (pinfunction "A_2") (pintype "input"))
      (node (ref "J3") (pin "3") (pinfunction "3_3") (pintype "passive"))
    )
    (net (code "185") (name "~{KFUN1}") (class "Default")
      (node (ref "E2") (pin "1") (pinfunction "SER_1") (pintype "input"))
      (node (ref "E2") (pin "2") (pinfunction "A_2") (pintype "input"))
      (node (ref "E26") (pin "3") (pinfunction "D2_3") (pintype "input"))
      (node (ref "J3") (pin "2") (pinfunction "2_2") (pintype "passive"))
    )
    (net (code "186") (name "~{KFUN2}") (class "Default")
      (node (ref "E1") (pin "1") (pinfunction "SER_1") (pintype "input"))
      (node (ref "E1") (pin "2") (pinfunction "A_2") (pintype "input"))
      (node (ref "E26") (pin "6") (pinfunction "D3_6") (pintype "input"))
      (node (ref "J3") (pin "1") (pinfunction "1_1") (pintype "passive"))
    )
    (net (code "187") (name "~{LAENAB}") (class "Default")
      (node (ref "E23") (pin "2") (pinfunction "O_2") (pintype "open_collector"))
      (node (ref "J2") (pin "22") (pinfunction "22_22") (pintype "passive"))
    )
    (net (code "188") (name "~{MAEN}") (class "Default")
      (node (ref "E23") (pin "8") (pinfunction "O_8") (pintype "open_collector"))
      (node (ref "J2") (pin "32") (pinfunction "32_32") (pintype "passive"))
    )
    (net (code "189") (name "~{MALC}") (class "Default")
      (node (ref "E28") (pin "11") (pinfunction "2Y1_11") (pintype "tri_state"))
      (node (ref "J2") (pin "36") (pinfunction "36_36") (pintype "passive"))
    )
    (net (code "190") (name "~{MCLOCK}") (class "Default")
      (node (ref "E33") (pin "2") (pinfunction "I0_2") (pintype "input"))
      (node (ref "J4") (pin "1") (pinfunction "1_1") (pintype "passive"))
    )
    (net (code "191") (name "~{MD}") (class "Default")
      (node (ref "E34") (pin "7") (pinfunction "1Y3_7") (pintype "tri_state"))
      (node (ref "J2") (pin "18") (pinfunction "18_18") (pintype "passive"))
    )
    (net (code "192") (name "~{MEMSTART}") (class "Default")
      (node (ref "E23") (pin "12") (pinfunction "O_12") (pintype "open_collector"))
      (node (ref "J2") (pin "26") (pinfunction "26_26") (pintype "passive"))
    )
    (net (code "193") (name "~{MH0}") (class "Default")
      (node (ref "E20") (pin "12") (pinfunction "D_12") (pintype "input"))
      (node (ref "E20") (pin "8") (pinfunction "~{Q}_8") (pintype "output"))
      (node (ref "E21") (pin "9") (pinfunction "I0_9") (pintype "input"))
      (node (ref "E8") (pin "2") (pinfunction "I1_2") (pintype "input"))
      (node (ref "E8") (pin "9") (pinfunction "I0_9") (pintype "input"))
    )
    (net (code "194") (name "~{MSIRDIS}") (class "Default")
      (node (ref "E31") (pin "11") (pinfunction "2Y1_11") (pintype "tri_state"))
      (node (ref "J2") (pin "2") (pinfunction "2_2") (pintype "passive"))
    )
    (net (code "195") (name "~{PANLOCK}") (class "Default")
      (node (ref "E24") (pin "13") (pinfunction "I_13") (pintype "input"))
      (node (ref "J2") (pin "6") (pinfunction "6_6") (pintype "passive"))
      (node (ref "R31") (pin "1") (pinfunction "1_1") (pintype "passive"))
    )
    (net (code "196") (name "~{PULSELOADADD}") (class "Default")
      (node (ref "E31") (pin "7") (pinfunction "1Y3_7") (pintype "tri_state"))
      (node (ref "J2") (pin "40") (pinfunction "40_40") (pintype "passive"))
    )
    (net (code "197") (name "~{RUN}") (class "Default")
      (node (ref "E24") (pin "5") (pinfunction "I_5") (pintype "input"))
      (node (ref "J1") (pin "18") (pinfunction "18_18") (pintype "passive"))
      (node (ref "R28") (pin "1") (pinfunction "1_1") (pintype "passive"))
    )
    (net (code "198") (name "~{SHLT}") (class "Default")
      (node (ref "E27") (pin "1") (pinfunction "I_1") (pintype "input"))
      (node (ref "J3") (pin "5") (pinfunction "5_5") (pintype "passive"))
    )
    (net (code "199") (name "~{SINGSTEP}") (class "Default")
      (node (ref "E28") (pin "13") (pinfunction "2Y2_13") (pintype "tri_state"))
      (node (ref "J2") (pin "14") (pinfunction "14_14") (pintype "passive"))
    )
    (net (code "200") (name "~{SRDATA}") (class "Default")
      (node (ref "E32") (pin "13") (pinfunction "I1_13") (pintype "input"))
      (node (ref "E8") (pin "1") (pinfunction "I0_1") (pintype "input"))
      (node (ref "J2") (pin "30") (pinfunction "30_30") (pintype "passive"))
      (node (ref "R29") (pin "1") (pinfunction "1_1") (pintype "passive"))
      (node (ref "R30") (pin "2") (pinfunction "2_2") (pintype "passive"))
    )
    (net (code "201") (name "~{STATE}") (class "Default")
      (node (ref "E34") (pin "11") (pinfunction "2Y1_11") (pintype "tri_state"))
      (node (ref "J2") (pin "38") (pinfunction "38_38") (pintype "passive"))
    )
    (net (code "202") (name "~{STHIS}") (class "Default")
      (node (ref "E20") (pin "2") (pinfunction "D_2") (pintype "input"))
      (node (ref "J3") (pin "4") (pinfunction "4_4") (pintype "passive"))
    )
    (net (code "203") (name "~{TS1}") (class "Default")
      (node (ref "E20") (pin "3") (pinfunction "CLK_3") (pintype "input"))
      (node (ref "E21") (pin "10") (pinfunction "I1_10") (pintype "input"))
      (node (ref "E24") (pin "9") (pinfunction "I_9") (pintype "input"))
      (node (ref "J1") (pin "26") (pinfunction "26_26") (pintype "passive"))
      (node (ref "R26") (pin "1") (pinfunction "1_1") (pintype "passive"))
      (node (ref "R27") (pin "2") (pinfunction "2_2") (pintype "passive"))
    )
  )
)
